# FMC_HPC2_RTM.net
KiCad netlist of a schematic drawn in Altium Designer
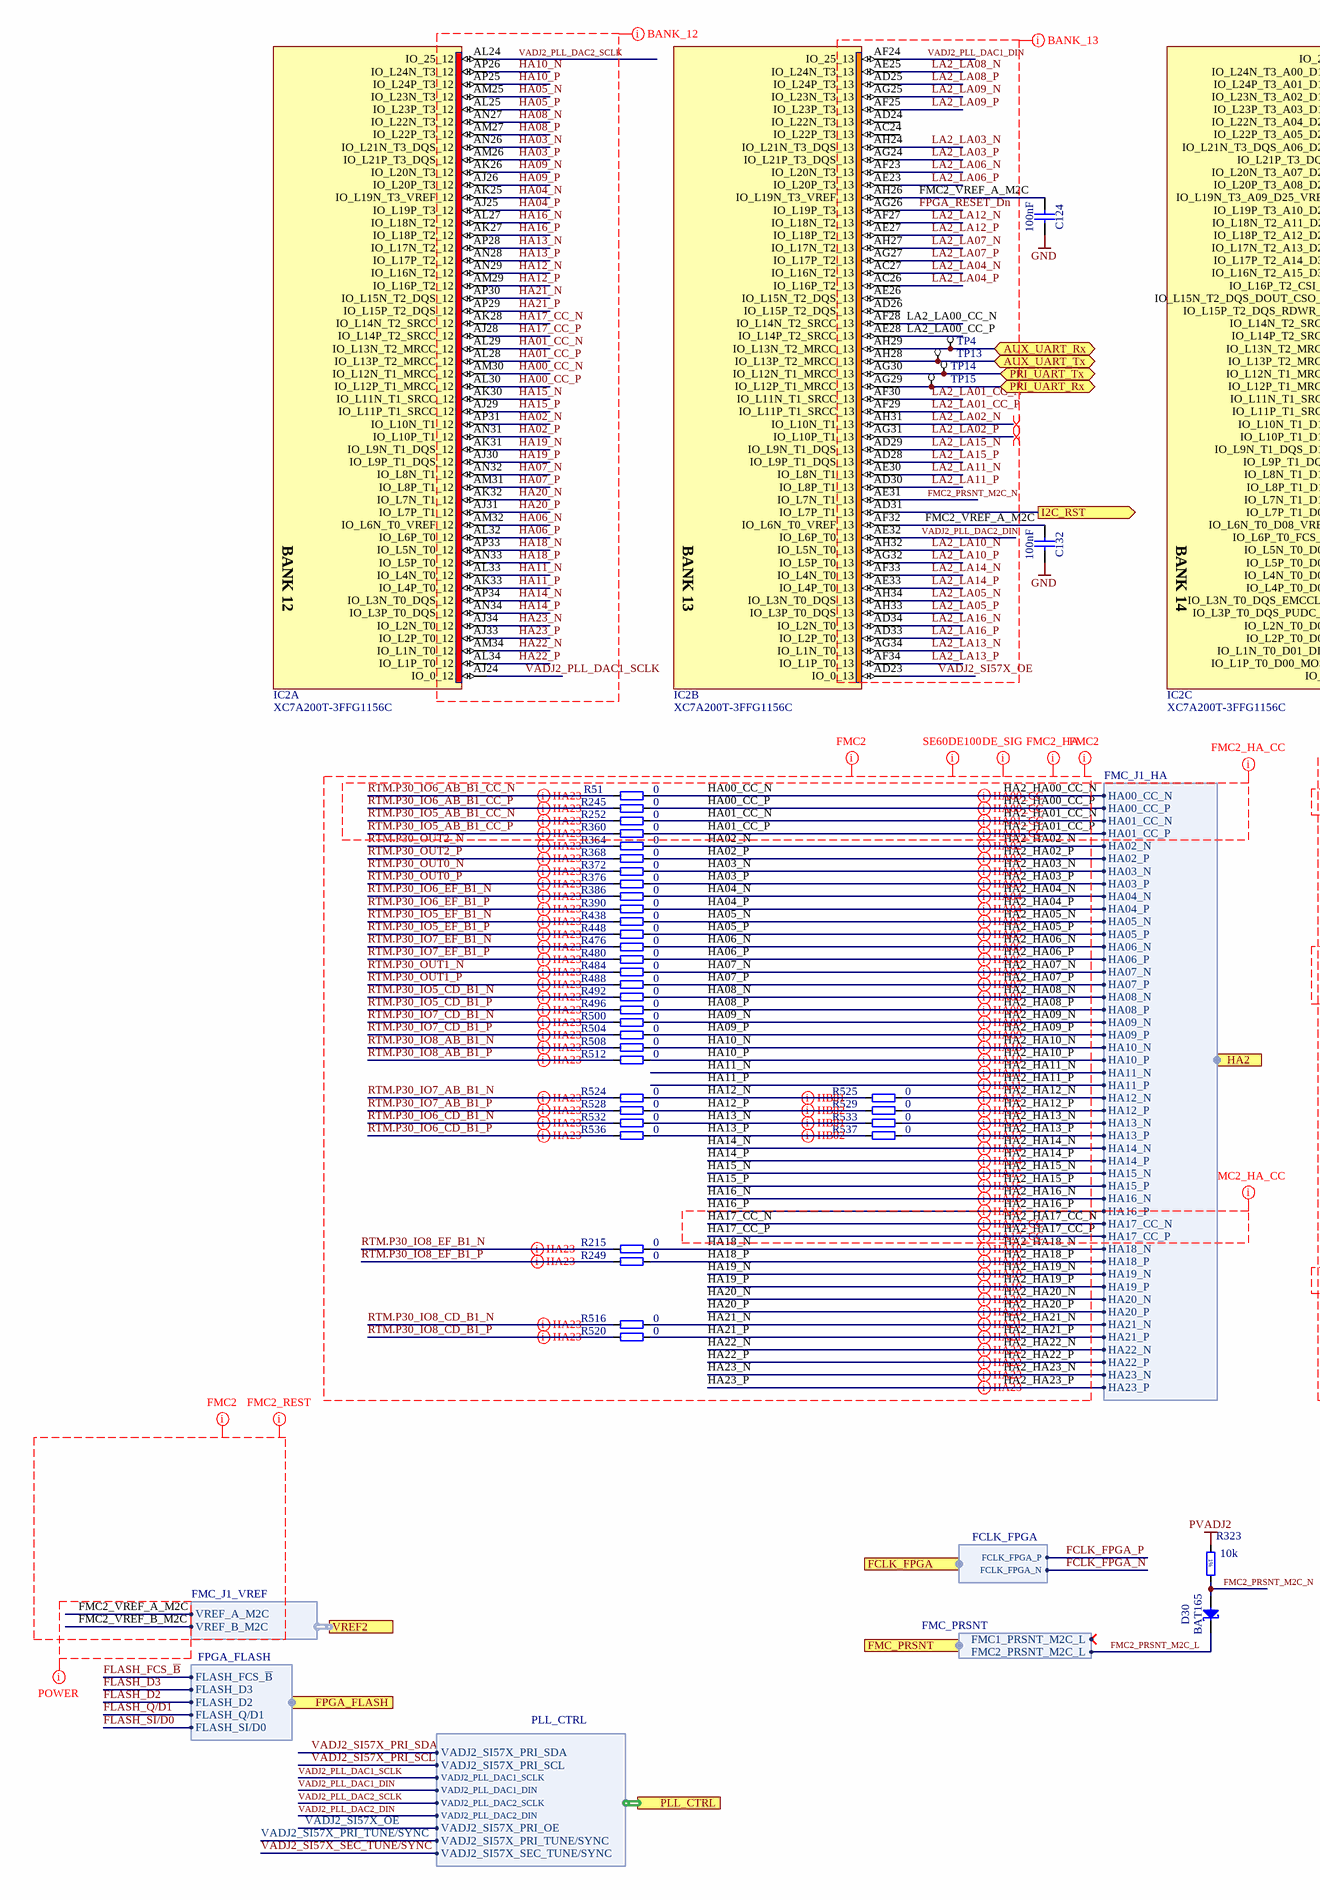
[diagram p0: FMC_HPC2_RTM.SchDoc, left]
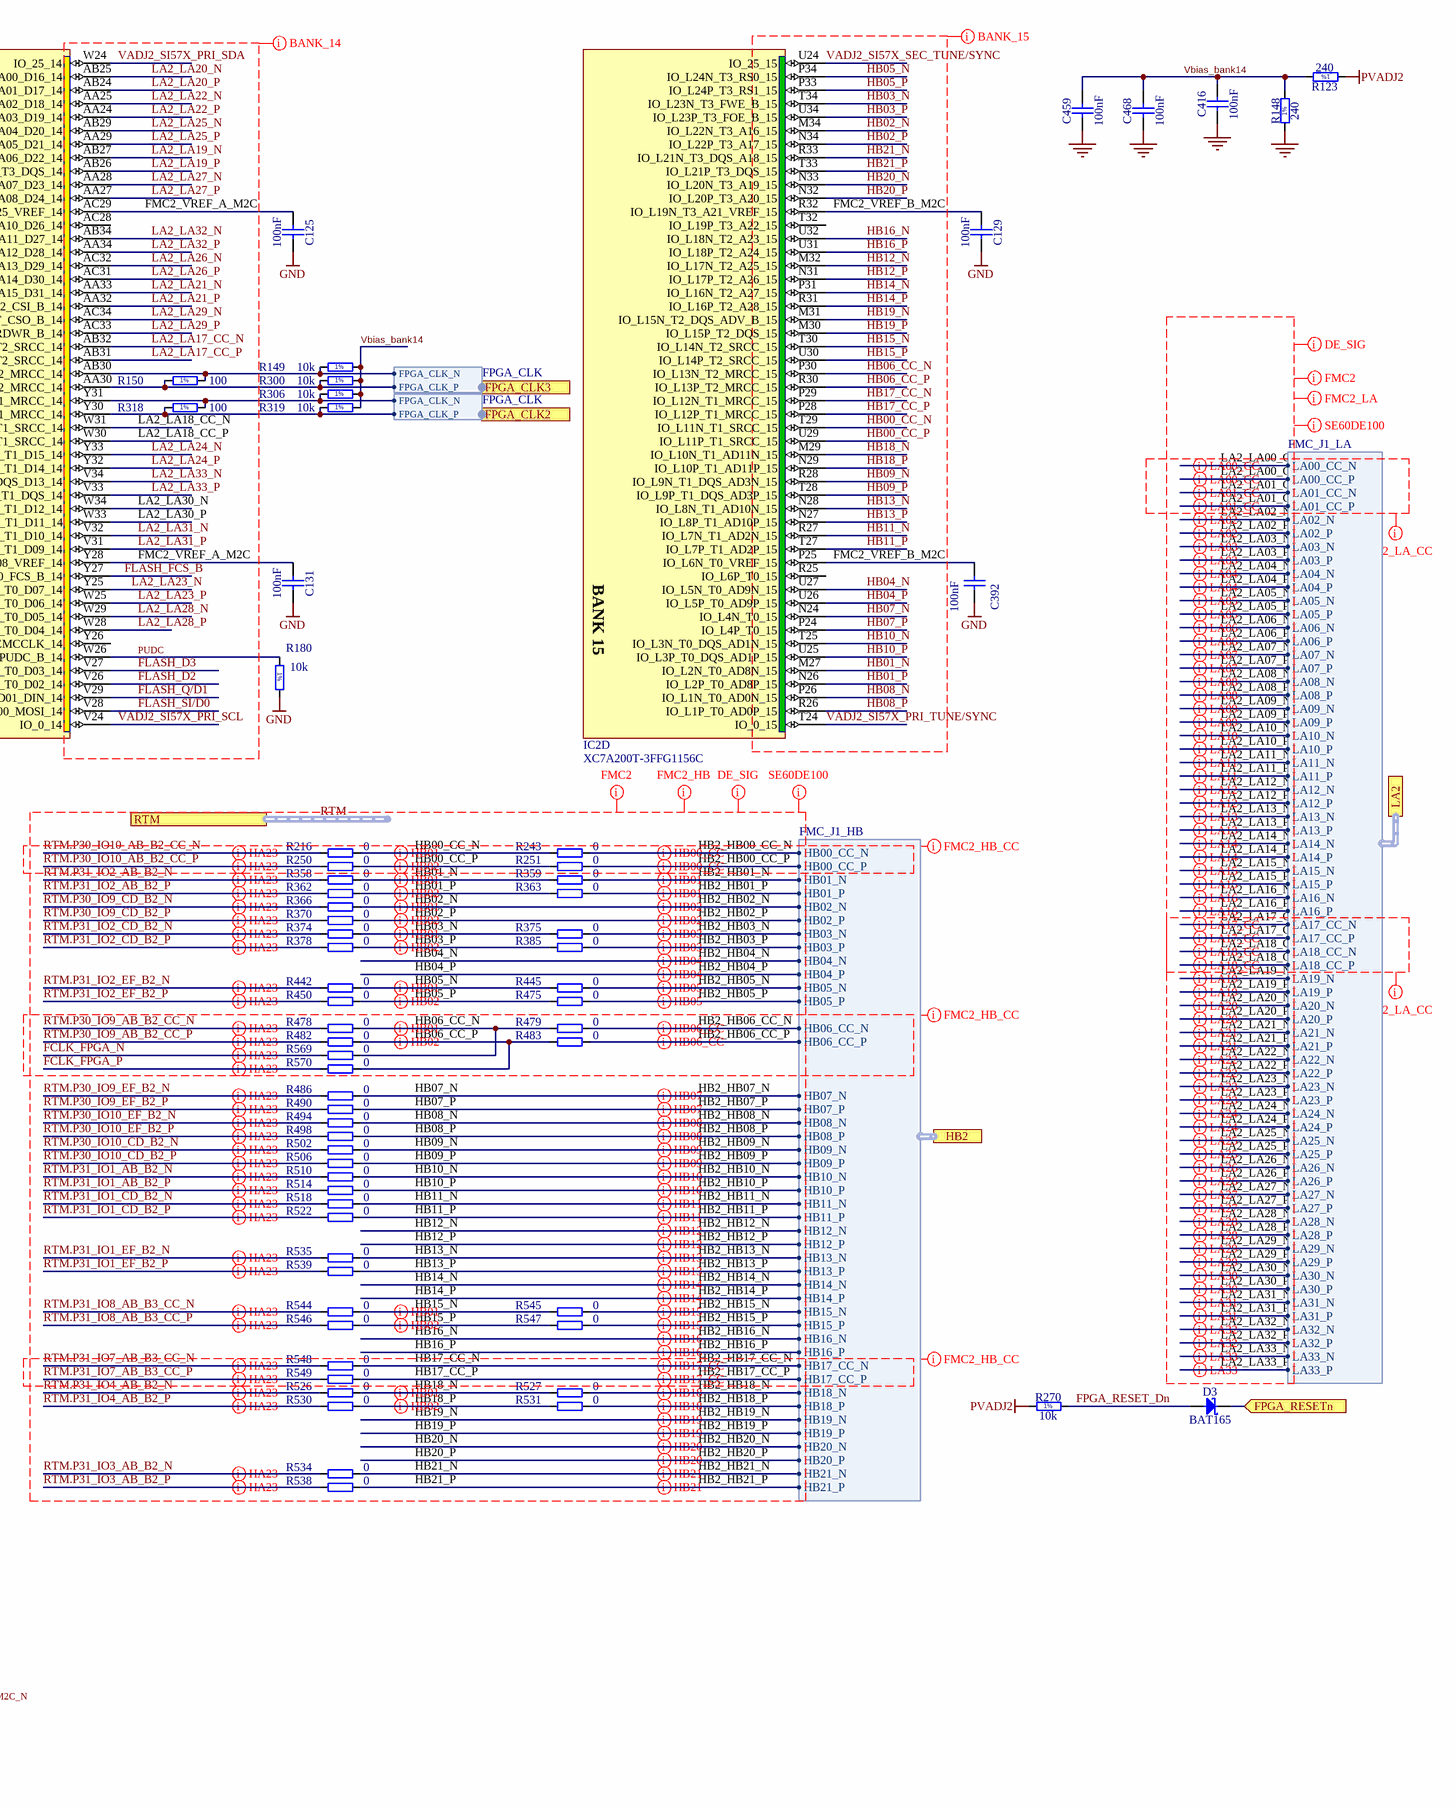
[diagram p1: FMC_HPC2_RTM.SchDoc, right]

(export (version "E")
  (design (tool "Eeschema 10.0.6"))
  (components
    (comp (ref "C124")
      (value "100nF")
      (footprint "CAPC0603X33N")
      (description "Non-polarised capacitor")
      (fields
        (field (name "PART NUMBER") "CC0201_100NF_6.3V_10%_X5R")
        (field (name "VOLTAGE") "6.3V")
        (field (name "AUTHOR") "CERN DEM JLC")
      )
      (libsource (lib "Capacitors") (part "Capacitor - non polarized"))
    )
    (comp (ref "C125")
      (value "100nF")
      (footprint "CAPC0603X33N")
      (description "Non-polarised capacitor")
      (fields
        (field (name "PART NUMBER") "CC0201_100NF_6.3V_10%_X5R")
        (field (name "VOLTAGE") "6.3V")
        (field (name "AUTHOR") "CERN DEM JLC")
      )
      (libsource (lib "Capacitors") (part "Capacitor - non polarized"))
    )
    (comp (ref "C129")
      (value "100nF")
      (footprint "CAPC0603X33N")
      (description "Non-polarised capacitor")
      (fields
        (field (name "PART NUMBER") "CC0201_100NF_6.3V_10%_X5R")
        (field (name "VOLTAGE") "6.3V")
        (field (name "AUTHOR") "CERN DEM JLC")
      )
      (libsource (lib "Capacitors") (part "Capacitor - non polarized"))
    )
    (comp (ref "C131")
      (value "100nF")
      (footprint "CAPC0603X33N")
      (description "Non-polarised capacitor")
      (fields
        (field (name "PART NUMBER") "CC0201_100NF_6.3V_10%_X5R")
        (field (name "VOLTAGE") "6.3V")
        (field (name "AUTHOR") "CERN DEM JLC")
      )
      (libsource (lib "Capacitors") (part "Capacitor - non polarized"))
    )
    (comp (ref "C132")
      (value "100nF")
      (footprint "CAPC0603X33N")
      (description "Non-polarised capacitor")
      (fields
        (field (name "PART NUMBER") "CC0201_100NF_6.3V_10%_X5R")
        (field (name "VOLTAGE") "6.3V")
        (field (name "AUTHOR") "CERN DEM JLC")
      )
      (libsource (lib "Capacitors") (part "Capacitor - non polarized"))
    )
    (comp (ref "C392")
      (value "100nF")
      (footprint "CAPC0603X33N")
      (description "Non-polarised capacitor")
      (fields
        (field (name "PART NUMBER") "CC0201_100NF_6.3V_10%_X5R")
        (field (name "VOLTAGE") "6.3V")
        (field (name "AUTHOR") "CERN DEM JLC")
      )
      (libsource (lib "Capacitors") (part "Capacitor - non polarized"))
    )
    (comp (ref "C416")
      (value "100nF")
      (footprint "CAPC0603X33N")
      (description "Non-polarised capacitor")
      (fields
        (field (name "MANUFACTURER PART NUMBER") "CC0201_100NF_6.3V_10%_X5R")
        (field (name "MANUFACTURER") "GENERIC")
        (field (name "AUTHOR") "CERN DEM JLC")
      )
      (libsource (lib "Capacitors") (part "Capacitor - non polarized"))
    )
    (comp (ref "C459")
      (value "100nF")
      (footprint "CAPC0603X33N")
      (description "Non-polarised capacitor")
      (fields
        (field (name "MANUFACTURER PART NUMBER") "CC0201_100NF_6.3V_10%_X5R")
        (field (name "MANUFACTURER") "GENERIC")
        (field (name "AUTHOR") "CERN DEM JLC")
      )
      (libsource (lib "Capacitors") (part "Capacitor - non polarized"))
    )
    (comp (ref "C468")
      (value "100nF")
      (footprint "CAPC0603X33N")
      (description "Non-polarised capacitor")
      (fields
        (field (name "MANUFACTURER PART NUMBER") "CC0201_100NF_6.3V_10%_X5R")
        (field (name "MANUFACTURER") "GENERIC")
        (field (name "AUTHOR") "CERN DEM JLC")
      )
      (libsource (lib "Capacitors") (part "Capacitor - non polarized"))
    )
    (comp (ref "D3")
      (value "BAT165")
      (footprint "SOD2512X110N")
      (description "Schottky Diode")
      (fields
        (field (name "VOLTAGE") "40V")
        (field (name "POWER") "750mA")
        (field (name "AUTHOR") "CERN DEM JLC")
      )
      (libsource (lib "ICs And Semiconductors") (part "Diode Schottky"))
    )
    (comp (ref "D30")
      (value "BAT165")
      (footprint "SOD2512X110N")
      (description "Schottky Diode")
      (fields
        (field (name "MANUFACTURER") "INFINEON")
        (field (name "VOLTAGE") "40V")
        (field (name "AUTHOR") "CERN DEM JLC")
      )
      (libsource (lib "ICs And Semiconductors") (part "Diode Schottky"))
    )
    (comp (ref "IC2")
      (value "XC7A200T-3FFG1156C")
      (footprint "BGA1156C100P34X34_3500X3500X335")
      (description "Artix-6 FPGA, 16 GTPs, 600 User I/Os, 1156-Pin BGA, Speed Grade 2, Commercial Grade, Pb-Free")
      (fields
        (field (name "MANUFACTURER") "XILINX")
        (field (name "MANUFACTURER PART NUMBER") "XC7A350T-2FFG1156C")
        (field (name "AUTHOR") "CERN DEM JLC")
      )
      (libsource (lib "AMC_FMC_Carrier") (part "XC7A200T-3FFG1156C"))
    )
    (comp (ref "R51")
      (value "0")
      (footprint "RESC0603X28N")
      (description "Resistor")
      (fields
        (field (name "PART NUMBER") "R0201_0R_JUMPER")
        (field (name "MANUFACTURER") "GENERIC")
        (field (name "AUTHOR") "CERN DEM JLC")
      )
      (libsource (lib "Resistors") (part "Resistor"))
    )
    (comp (ref "R123")
      (value "240")
      (footprint "RESC1005X40N")
      (description "Resistor - 1%")
      (fields
        (field (name "MANUFACTURER PART NUMBER") "R0402_240R_1%_0.0625W_100PPM")
        (field (name "MANUFACTURER") "GENERIC")
        (field (name "AUTHOR") "CERN DEM JLC")
      )
      (libsource (lib "Resistors") (part "Resistor - 1%"))
    )
    (comp (ref "R148")
      (value "240")
      (footprint "RESC1005X40N")
      (description "Resistor - 1%")
      (fields
        (field (name "MANUFACTURER PART NUMBER") "R0402_240R_1%_0.0625W_100PPM")
        (field (name "MANUFACTURER") "GENERIC")
        (field (name "AUTHOR") "CERN DEM JLC")
      )
      (libsource (lib "Resistors") (part "Resistor - 1%"))
    )
    (comp (ref "R149")
      (value "10k")
      (footprint "RESC1005X40N")
      (description "Resistor - 1%")
      (fields
        (field (name "MANUFACTURER PART NUMBER") "R0402_10K_1%_0.0625W_100PPM")
        (field (name "MANUFACTURER") "GENERIC")
        (field (name "AUTHOR") "CERN DEM JLC")
      )
      (libsource (lib "Resistors") (part "Resistor - 1%"))
    )
    (comp (ref "R150")
      (value "100")
      (footprint "RESC0603X28N")
      (description "Resistor - 1%")
      (fields
        (field (name "MANUFACTURER PART NUMBER") "R0201_100R_1%_0.05W_200PPM")
        (field (name "MANUFACTURER") "GENERIC")
        (field (name "AUTHOR") "CERN DEM JLC")
      )
      (libsource (lib "Resistors") (part "Resistor - 1%"))
    )
    (comp (ref "R180")
      (value "10k")
      (footprint "RESC1005X40N")
      (description "Resistor - 1%")
      (fields
        (field (name "PART NUMBER") "R0402_10K_1%_0.0625W_100PPM")
        (field (name "POWER") "0.0625W")
        (field (name "AUTHOR") "CERN DEM JLC")
      )
      (libsource (lib "Resistors") (part "Resistor - 1%"))
    )
    (comp (ref "R215")
      (value "0")
      (footprint "RESC0603X28N")
      (description "Resistor")
      (fields
        (field (name "PART NUMBER") "R0201_0R_JUMPER")
        (field (name "MANUFACTURER") "GENERIC")
        (field (name "AUTHOR") "CERN DEM JLC")
      )
      (libsource (lib "Resistors") (part "Resistor"))
    )
    (comp (ref "R216")
      (value "0")
      (footprint "RESC0603X28N")
      (description "Resistor")
      (fields
        (field (name "PART NUMBER") "R0201_0R_JUMPER")
        (field (name "MANUFACTURER") "GENERIC")
        (field (name "AUTHOR") "CERN DEM JLC")
      )
      (libsource (lib "Resistors") (part "Resistor"))
    )
    (comp (ref "R243")
      (value "0")
      (footprint "RESC0603X28N")
      (description "Resistor")
      (fields
        (field (name "PART NUMBER") "R0201_0R_JUMPER")
        (field (name "MANUFACTURER") "GENERIC")
        (field (name "AUTHOR") "CERN DEM JLC")
      )
      (libsource (lib "Resistors") (part "Resistor"))
    )
    (comp (ref "R245")
      (value "0")
      (footprint "RESC0603X28N")
      (description "Resistor")
      (fields
        (field (name "PART NUMBER") "R0201_0R_JUMPER")
        (field (name "MANUFACTURER") "GENERIC")
        (field (name "AUTHOR") "CERN DEM JLC")
      )
      (libsource (lib "Resistors") (part "Resistor"))
    )
    (comp (ref "R249")
      (value "0")
      (footprint "RESC0603X28N")
      (description "Resistor")
      (fields
        (field (name "PART NUMBER") "R0201_0R_JUMPER")
        (field (name "MANUFACTURER") "GENERIC")
        (field (name "AUTHOR") "CERN DEM JLC")
      )
      (libsource (lib "Resistors") (part "Resistor"))
    )
    (comp (ref "R250")
      (value "0")
      (footprint "RESC0603X28N")
      (description "Resistor")
      (fields
        (field (name "PART NUMBER") "R0201_0R_JUMPER")
        (field (name "MANUFACTURER") "GENERIC")
        (field (name "AUTHOR") "CERN DEM JLC")
      )
      (libsource (lib "Resistors") (part "Resistor"))
    )
    (comp (ref "R251")
      (value "0")
      (footprint "RESC0603X28N")
      (description "Resistor")
      (fields
        (field (name "PART NUMBER") "R0201_0R_JUMPER")
        (field (name "MANUFACTURER") "GENERIC")
        (field (name "AUTHOR") "CERN DEM JLC")
      )
      (libsource (lib "Resistors") (part "Resistor"))
    )
    (comp (ref "R252")
      (value "0")
      (footprint "RESC0603X28N")
      (description "Resistor")
      (fields
        (field (name "PART NUMBER") "R0201_0R_JUMPER")
        (field (name "MANUFACTURER") "GENERIC")
        (field (name "AUTHOR") "CERN DEM JLC")
      )
      (libsource (lib "Resistors") (part "Resistor"))
    )
    (comp (ref "R270")
      (value "10k")
      (footprint "RESC1005X40N")
      (description "Resistor - 1%")
      (fields
        (field (name "PART NUMBER") "R0402_10K_1%_0.0625W_100PPM")
        (field (name "POWER") "0.0625W")
        (field (name "AUTHOR") "CERN DEM JLC")
      )
      (libsource (lib "Resistors") (part "Resistor - 1%"))
    )
    (comp (ref "R300")
      (value "10k")
      (footprint "RESC1005X40N")
      (description "Resistor - 1%")
      (fields
        (field (name "MANUFACTURER PART NUMBER") "R0402_10K_1%_0.0625W_100PPM")
        (field (name "MANUFACTURER") "GENERIC")
        (field (name "AUTHOR") "CERN DEM JLC")
      )
      (libsource (lib "Resistors") (part "Resistor - 1%"))
    )
    (comp (ref "R306")
      (value "10k")
      (footprint "RESC1005X40N")
      (description "Resistor - 1%")
      (fields
        (field (name "MANUFACTURER PART NUMBER") "R0402_10K_1%_0.0625W_100PPM")
        (field (name "MANUFACTURER") "GENERIC")
        (field (name "AUTHOR") "CERN DEM JLC")
      )
      (libsource (lib "Resistors") (part "Resistor - 1%"))
    )
    (comp (ref "R318")
      (value "100")
      (footprint "RESC0603X28N")
      (description "Resistor - 1%")
      (fields
        (field (name "MANUFACTURER PART NUMBER") "R0201_100R_1%_0.05W_200PPM")
        (field (name "MANUFACTURER") "GENERIC")
        (field (name "AUTHOR") "CERN DEM JLC")
      )
      (libsource (lib "Resistors") (part "Resistor - 1%"))
    )
    (comp (ref "R319")
      (value "10k")
      (footprint "RESC1005X40N")
      (description "Resistor - 1%")
      (fields
        (field (name "MANUFACTURER PART NUMBER") "R0402_10K_1%_0.0625W_100PPM")
        (field (name "MANUFACTURER") "GENERIC")
        (field (name "AUTHOR") "CERN DEM JLC")
      )
      (libsource (lib "Resistors") (part "Resistor - 1%"))
    )
    (comp (ref "R323")
      (value "10k")
      (footprint "RESC1005X40N")
      (description "Resistor - 1%")
      (fields
        (field (name "PART NUMBER") "R0402_10K_1%_0.0625W_100PPM")
        (field (name "POWER") "0.0625W")
        (field (name "AUTHOR") "CERN DEM JLC")
      )
      (libsource (lib "Resistors") (part "Resistor - 1%"))
    )
    (comp (ref "R358")
      (value "0")
      (footprint "RESC0603X28N")
      (description "Resistor")
      (fields
        (field (name "PART NUMBER") "R0201_0R_JUMPER")
        (field (name "MANUFACTURER") "GENERIC")
        (field (name "AUTHOR") "CERN DEM JLC")
      )
      (libsource (lib "Resistors") (part "Resistor"))
    )
    (comp (ref "R359")
      (value "0")
      (footprint "RESC0603X28N")
      (description "Resistor")
      (fields
        (field (name "PART NUMBER") "R0201_0R_JUMPER")
        (field (name "MANUFACTURER") "GENERIC")
        (field (name "AUTHOR") "CERN DEM JLC")
      )
      (libsource (lib "Resistors") (part "Resistor"))
    )
    (comp (ref "R360")
      (value "0")
      (footprint "RESC0603X28N")
      (description "Resistor")
      (fields
        (field (name "PART NUMBER") "R0201_0R_JUMPER")
        (field (name "MANUFACTURER") "GENERIC")
        (field (name "AUTHOR") "CERN DEM JLC")
      )
      (libsource (lib "Resistors") (part "Resistor"))
    )
    (comp (ref "R362")
      (value "0")
      (footprint "RESC0603X28N")
      (description "Resistor")
      (fields
        (field (name "PART NUMBER") "R0201_0R_JUMPER")
        (field (name "MANUFACTURER") "GENERIC")
        (field (name "AUTHOR") "CERN DEM JLC")
      )
      (libsource (lib "Resistors") (part "Resistor"))
    )
    (comp (ref "R363")
      (value "0")
      (footprint "RESC0603X28N")
      (description "Resistor")
      (fields
        (field (name "PART NUMBER") "R0201_0R_JUMPER")
        (field (name "MANUFACTURER") "GENERIC")
        (field (name "AUTHOR") "CERN DEM JLC")
      )
      (libsource (lib "Resistors") (part "Resistor"))
    )
    (comp (ref "R364")
      (value "0")
      (footprint "RESC0603X28N")
      (description "Resistor")
      (fields
        (field (name "PART NUMBER") "R0201_0R_JUMPER")
        (field (name "MANUFACTURER") "GENERIC")
        (field (name "AUTHOR") "CERN DEM JLC")
      )
      (libsource (lib "Resistors") (part "Resistor"))
    )
    (comp (ref "R366")
      (value "0")
      (footprint "RESC0603X28N")
      (description "Resistor")
      (fields
        (field (name "PART NUMBER") "R0201_0R_JUMPER")
        (field (name "MANUFACTURER") "GENERIC")
        (field (name "AUTHOR") "CERN DEM JLC")
      )
      (libsource (lib "Resistors") (part "Resistor"))
    )
    (comp (ref "R368")
      (value "0")
      (footprint "RESC0603X28N")
      (description "Resistor")
      (fields
        (field (name "PART NUMBER") "R0201_0R_JUMPER")
        (field (name "MANUFACTURER") "GENERIC")
        (field (name "AUTHOR") "CERN DEM JLC")
      )
      (libsource (lib "Resistors") (part "Resistor"))
    )
    (comp (ref "R370")
      (value "0")
      (footprint "RESC0603X28N")
      (description "Resistor")
      (fields
        (field (name "PART NUMBER") "R0201_0R_JUMPER")
        (field (name "MANUFACTURER") "GENERIC")
        (field (name "AUTHOR") "CERN DEM JLC")
      )
      (libsource (lib "Resistors") (part "Resistor"))
    )
    (comp (ref "R372")
      (value "0")
      (footprint "RESC0603X28N")
      (description "Resistor")
      (fields
        (field (name "PART NUMBER") "R0201_0R_JUMPER")
        (field (name "MANUFACTURER") "GENERIC")
        (field (name "AUTHOR") "CERN DEM JLC")
      )
      (libsource (lib "Resistors") (part "Resistor"))
    )
    (comp (ref "R374")
      (value "0")
      (footprint "RESC0603X28N")
      (description "Resistor")
      (fields
        (field (name "PART NUMBER") "R0201_0R_JUMPER")
        (field (name "MANUFACTURER") "GENERIC")
        (field (name "AUTHOR") "CERN DEM JLC")
      )
      (libsource (lib "Resistors") (part "Resistor"))
    )
    (comp (ref "R375")
      (value "0")
      (footprint "RESC0603X28N")
      (description "Resistor")
      (fields
        (field (name "PART NUMBER") "R0201_0R_JUMPER")
        (field (name "MANUFACTURER") "GENERIC")
        (field (name "AUTHOR") "CERN DEM JLC")
      )
      (libsource (lib "Resistors") (part "Resistor"))
    )
    (comp (ref "R376")
      (value "0")
      (footprint "RESC0603X28N")
      (description "Resistor")
      (fields
        (field (name "PART NUMBER") "R0201_0R_JUMPER")
        (field (name "MANUFACTURER") "GENERIC")
        (field (name "AUTHOR") "CERN DEM JLC")
      )
      (libsource (lib "Resistors") (part "Resistor"))
    )
    (comp (ref "R378")
      (value "0")
      (footprint "RESC0603X28N")
      (description "Resistor")
      (fields
        (field (name "PART NUMBER") "R0201_0R_JUMPER")
        (field (name "MANUFACTURER") "GENERIC")
        (field (name "AUTHOR") "CERN DEM JLC")
      )
      (libsource (lib "Resistors") (part "Resistor"))
    )
    (comp (ref "R385")
      (value "0")
      (footprint "RESC0603X28N")
      (description "Resistor")
      (fields
        (field (name "PART NUMBER") "R0201_0R_JUMPER")
        (field (name "MANUFACTURER") "GENERIC")
        (field (name "AUTHOR") "CERN DEM JLC")
      )
      (libsource (lib "Resistors") (part "Resistor"))
    )
    (comp (ref "R386")
      (value "0")
      (footprint "RESC0603X28N")
      (description "Resistor")
      (fields
        (field (name "PART NUMBER") "R0201_0R_JUMPER")
        (field (name "MANUFACTURER") "GENERIC")
        (field (name "AUTHOR") "CERN DEM JLC")
      )
      (libsource (lib "Resistors") (part "Resistor"))
    )
    (comp (ref "R390")
      (value "0")
      (footprint "RESC0603X28N")
      (description "Resistor")
      (fields
        (field (name "PART NUMBER") "R0201_0R_JUMPER")
        (field (name "MANUFACTURER") "GENERIC")
        (field (name "AUTHOR") "CERN DEM JLC")
      )
      (libsource (lib "Resistors") (part "Resistor"))
    )
    (comp (ref "R438")
      (value "0")
      (footprint "RESC0603X28N")
      (description "Resistor")
      (fields
        (field (name "PART NUMBER") "R0201_0R_JUMPER")
        (field (name "MANUFACTURER") "GENERIC")
        (field (name "AUTHOR") "CERN DEM JLC")
      )
      (libsource (lib "Resistors") (part "Resistor"))
    )
    (comp (ref "R442")
      (value "0")
      (footprint "RESC0603X28N")
      (description "Resistor")
      (fields
        (field (name "PART NUMBER") "R0201_0R_JUMPER")
        (field (name "MANUFACTURER") "GENERIC")
        (field (name "AUTHOR") "CERN DEM JLC")
      )
      (libsource (lib "Resistors") (part "Resistor"))
    )
    (comp (ref "R445")
      (value "0")
      (footprint "RESC0603X28N")
      (description "Resistor")
      (fields
        (field (name "PART NUMBER") "R0201_0R_JUMPER")
        (field (name "MANUFACTURER") "GENERIC")
        (field (name "AUTHOR") "CERN DEM JLC")
      )
      (libsource (lib "Resistors") (part "Resistor"))
    )
    (comp (ref "R448")
      (value "0")
      (footprint "RESC0603X28N")
      (description "Resistor")
      (fields
        (field (name "PART NUMBER") "R0201_0R_JUMPER")
        (field (name "MANUFACTURER") "GENERIC")
        (field (name "AUTHOR") "CERN DEM JLC")
      )
      (libsource (lib "Resistors") (part "Resistor"))
    )
    (comp (ref "R450")
      (value "0")
      (footprint "RESC0603X28N")
      (description "Resistor")
      (fields
        (field (name "PART NUMBER") "R0201_0R_JUMPER")
        (field (name "MANUFACTURER") "GENERIC")
        (field (name "AUTHOR") "CERN DEM JLC")
      )
      (libsource (lib "Resistors") (part "Resistor"))
    )
    (comp (ref "R475")
      (value "0")
      (footprint "RESC0603X28N")
      (description "Resistor")
      (fields
        (field (name "PART NUMBER") "R0201_0R_JUMPER")
        (field (name "MANUFACTURER") "GENERIC")
        (field (name "AUTHOR") "CERN DEM JLC")
      )
      (libsource (lib "Resistors") (part "Resistor"))
    )
    (comp (ref "R476")
      (value "0")
      (footprint "RESC0603X28N")
      (description "Resistor")
      (fields
        (field (name "PART NUMBER") "R0201_0R_JUMPER")
        (field (name "MANUFACTURER") "GENERIC")
        (field (name "AUTHOR") "CERN DEM JLC")
      )
      (libsource (lib "Resistors") (part "Resistor"))
    )
    (comp (ref "R478")
      (value "0")
      (footprint "RESC0603X28N")
      (description "Resistor")
      (fields
        (field (name "PART NUMBER") "R0201_0R_JUMPER")
        (field (name "MANUFACTURER") "GENERIC")
        (field (name "AUTHOR") "CERN DEM JLC")
      )
      (libsource (lib "Resistors") (part "Resistor"))
    )
    (comp (ref "R479")
      (value "0")
      (footprint "RESC0603X28N")
      (description "Resistor")
      (fields
        (field (name "PART NUMBER") "R0201_0R_JUMPER")
        (field (name "MANUFACTURER") "GENERIC")
        (field (name "AUTHOR") "CERN DEM JLC")
      )
      (libsource (lib "Resistors") (part "Resistor"))
    )
    (comp (ref "R480")
      (value "0")
      (footprint "RESC0603X28N")
      (description "Resistor")
      (fields
        (field (name "PART NUMBER") "R0201_0R_JUMPER")
        (field (name "MANUFACTURER") "GENERIC")
        (field (name "AUTHOR") "CERN DEM JLC")
      )
      (libsource (lib "Resistors") (part "Resistor"))
    )
    (comp (ref "R482")
      (value "0")
      (footprint "RESC0603X28N")
      (description "Resistor")
      (fields
        (field (name "PART NUMBER") "R0201_0R_JUMPER")
        (field (name "MANUFACTURER") "GENERIC")
        (field (name "AUTHOR") "CERN DEM JLC")
      )
      (libsource (lib "Resistors") (part "Resistor"))
    )
    (comp (ref "R483")
      (value "0")
      (footprint "RESC0603X28N")
      (description "Resistor")
      (fields
        (field (name "PART NUMBER") "R0201_0R_JUMPER")
        (field (name "MANUFACTURER") "GENERIC")
        (field (name "AUTHOR") "CERN DEM JLC")
      )
      (libsource (lib "Resistors") (part "Resistor"))
    )
    (comp (ref "R484")
      (value "0")
      (footprint "RESC0603X28N")
      (description "Resistor")
      (fields
        (field (name "PART NUMBER") "R0201_0R_JUMPER")
        (field (name "MANUFACTURER") "GENERIC")
        (field (name "AUTHOR") "CERN DEM JLC")
      )
      (libsource (lib "Resistors") (part "Resistor"))
    )
    (comp (ref "R486")
      (value "0")
      (footprint "RESC0603X28N")
      (description "Resistor")
      (fields
        (field (name "PART NUMBER") "R0201_0R_JUMPER")
        (field (name "MANUFACTURER") "GENERIC")
        (field (name "AUTHOR") "CERN DEM JLC")
      )
      (libsource (lib "Resistors") (part "Resistor"))
    )
    (comp (ref "R488")
      (value "0")
      (footprint "RESC0603X28N")
      (description "Resistor")
      (fields
        (field (name "PART NUMBER") "R0201_0R_JUMPER")
        (field (name "MANUFACTURER") "GENERIC")
        (field (name "AUTHOR") "CERN DEM JLC")
      )
      (libsource (lib "Resistors") (part "Resistor"))
    )
    (comp (ref "R490")
      (value "0")
      (footprint "RESC0603X28N")
      (description "Resistor")
      (fields
        (field (name "PART NUMBER") "R0201_0R_JUMPER")
        (field (name "MANUFACTURER") "GENERIC")
        (field (name "AUTHOR") "CERN DEM JLC")
      )
      (libsource (lib "Resistors") (part "Resistor"))
    )
    (comp (ref "R492")
      (value "0")
      (footprint "RESC0603X28N")
      (description "Resistor")
      (fields
        (field (name "PART NUMBER") "R0201_0R_JUMPER")
        (field (name "MANUFACTURER") "GENERIC")
        (field (name "AUTHOR") "CERN DEM JLC")
      )
      (libsource (lib "Resistors") (part "Resistor"))
    )
    (comp (ref "R494")
      (value "0")
      (footprint "RESC0603X28N")
      (description "Resistor")
      (fields
        (field (name "PART NUMBER") "R0201_0R_JUMPER")
        (field (name "MANUFACTURER") "GENERIC")
        (field (name "AUTHOR") "CERN DEM JLC")
      )
      (libsource (lib "Resistors") (part "Resistor"))
    )
    (comp (ref "R496")
      (value "0")
      (footprint "RESC0603X28N")
      (description "Resistor")
      (fields
        (field (name "PART NUMBER") "R0201_0R_JUMPER")
        (field (name "MANUFACTURER") "GENERIC")
        (field (name "AUTHOR") "CERN DEM JLC")
      )
      (libsource (lib "Resistors") (part "Resistor"))
    )
    (comp (ref "R498")
      (value "0")
      (footprint "RESC0603X28N")
      (description "Resistor")
      (fields
        (field (name "PART NUMBER") "R0201_0R_JUMPER")
        (field (name "MANUFACTURER") "GENERIC")
        (field (name "AUTHOR") "CERN DEM JLC")
      )
      (libsource (lib "Resistors") (part "Resistor"))
    )
    (comp (ref "R500")
      (value "0")
      (footprint "RESC0603X28N")
      (description "Resistor")
      (fields
        (field (name "PART NUMBER") "R0201_0R_JUMPER")
        (field (name "MANUFACTURER") "GENERIC")
        (field (name "AUTHOR") "CERN DEM JLC")
      )
      (libsource (lib "Resistors") (part "Resistor"))
    )
    (comp (ref "R502")
      (value "0")
      (footprint "RESC0603X28N")
      (description "Resistor")
      (fields
        (field (name "PART NUMBER") "R0201_0R_JUMPER")
        (field (name "MANUFACTURER") "GENERIC")
        (field (name "AUTHOR") "CERN DEM JLC")
      )
      (libsource (lib "Resistors") (part "Resistor"))
    )
    (comp (ref "R504")
      (value "0")
      (footprint "RESC0603X28N")
      (description "Resistor")
      (fields
        (field (name "PART NUMBER") "R0201_0R_JUMPER")
        (field (name "MANUFACTURER") "GENERIC")
        (field (name "AUTHOR") "CERN DEM JLC")
      )
      (libsource (lib "Resistors") (part "Resistor"))
    )
    (comp (ref "R506")
      (value "0")
      (footprint "RESC0603X28N")
      (description "Resistor")
      (fields
        (field (name "PART NUMBER") "R0201_0R_JUMPER")
        (field (name "MANUFACTURER") "GENERIC")
        (field (name "AUTHOR") "CERN DEM JLC")
      )
      (libsource (lib "Resistors") (part "Resistor"))
    )
    (comp (ref "R508")
      (value "0")
      (footprint "RESC0603X28N")
      (description "Resistor")
      (fields
        (field (name "PART NUMBER") "R0201_0R_JUMPER")
        (field (name "MANUFACTURER") "GENERIC")
        (field (name "AUTHOR") "CERN DEM JLC")
      )
      (libsource (lib "Resistors") (part "Resistor"))
    )
    (comp (ref "R510")
      (value "0")
      (footprint "RESC0603X28N")
      (description "Resistor")
      (fields
        (field (name "PART NUMBER") "R0201_0R_JUMPER")
        (field (name "MANUFACTURER") "GENERIC")
        (field (name "AUTHOR") "CERN DEM JLC")
      )
      (libsource (lib "Resistors") (part "Resistor"))
    )
    (comp (ref "R512")
      (value "0")
      (footprint "RESC0603X28N")
      (description "Resistor")
      (fields
        (field (name "PART NUMBER") "R0201_0R_JUMPER")
        (field (name "MANUFACTURER") "GENERIC")
        (field (name "AUTHOR") "CERN DEM JLC")
      )
      (libsource (lib "Resistors") (part "Resistor"))
    )
    (comp (ref "R514")
      (value "0")
      (footprint "RESC0603X28N")
      (description "Resistor")
      (fields
        (field (name "PART NUMBER") "R0201_0R_JUMPER")
        (field (name "MANUFACTURER") "GENERIC")
        (field (name "AUTHOR") "CERN DEM JLC")
      )
      (libsource (lib "Resistors") (part "Resistor"))
    )
    (comp (ref "R516")
      (value "0")
      (footprint "RESC0603X28N")
      (description "Resistor")
      (fields
        (field (name "PART NUMBER") "R0201_0R_JUMPER")
        (field (name "MANUFACTURER") "GENERIC")
        (field (name "AUTHOR") "CERN DEM JLC")
      )
      (libsource (lib "Resistors") (part "Resistor"))
    )
    (comp (ref "R518")
      (value "0")
      (footprint "RESC0603X28N")
      (description "Resistor")
      (fields
        (field (name "PART NUMBER") "R0201_0R_JUMPER")
        (field (name "MANUFACTURER") "GENERIC")
        (field (name "AUTHOR") "CERN DEM JLC")
      )
      (libsource (lib "Resistors") (part "Resistor"))
    )
    (comp (ref "R520")
      (value "0")
      (footprint "RESC0603X28N")
      (description "Resistor")
      (fields
        (field (name "PART NUMBER") "R0201_0R_JUMPER")
        (field (name "MANUFACTURER") "GENERIC")
        (field (name "AUTHOR") "CERN DEM JLC")
      )
      (libsource (lib "Resistors") (part "Resistor"))
    )
    (comp (ref "R522")
      (value "0")
      (footprint "RESC0603X28N")
      (description "Resistor")
      (fields
        (field (name "PART NUMBER") "R0201_0R_JUMPER")
        (field (name "MANUFACTURER") "GENERIC")
        (field (name "AUTHOR") "CERN DEM JLC")
      )
      (libsource (lib "Resistors") (part "Resistor"))
    )
    (comp (ref "R524")
      (value "0")
      (footprint "RESC0603X28N")
      (description "Resistor")
      (fields
        (field (name "PART NUMBER") "R0201_0R_JUMPER")
        (field (name "MANUFACTURER") "GENERIC")
        (field (name "AUTHOR") "CERN DEM JLC")
      )
      (libsource (lib "Resistors") (part "Resistor"))
    )
    (comp (ref "R525")
      (value "0")
      (footprint "RESC0603X28N")
      (description "Resistor")
      (fields
        (field (name "PART NUMBER") "R0201_0R_JUMPER")
        (field (name "MANUFACTURER") "GENERIC")
        (field (name "AUTHOR") "CERN DEM JLC")
      )
      (libsource (lib "Resistors") (part "Resistor"))
    )
    (comp (ref "R526")
      (value "0")
      (footprint "RESC0603X28N")
      (description "Resistor")
      (fields
        (field (name "PART NUMBER") "R0201_0R_JUMPER")
        (field (name "MANUFACTURER") "GENERIC")
        (field (name "AUTHOR") "CERN DEM JLC")
      )
      (libsource (lib "Resistors") (part "Resistor"))
    )
    (comp (ref "R527")
      (value "0")
      (footprint "RESC0603X28N")
      (description "Resistor")
      (fields
        (field (name "PART NUMBER") "R0201_0R_JUMPER")
        (field (name "MANUFACTURER") "GENERIC")
        (field (name "AUTHOR") "CERN DEM JLC")
      )
      (libsource (lib "Resistors") (part "Resistor"))
    )
    (comp (ref "R528")
      (value "0")
      (footprint "RESC0603X28N")
      (description "Resistor")
      (fields
        (field (name "PART NUMBER") "R0201_0R_JUMPER")
        (field (name "MANUFACTURER") "GENERIC")
        (field (name "AUTHOR") "CERN DEM JLC")
      )
      (libsource (lib "Resistors") (part "Resistor"))
    )
    (comp (ref "R529")
      (value "0")
      (footprint "RESC0603X28N")
      (description "Resistor")
      (fields
        (field (name "PART NUMBER") "R0201_0R_JUMPER")
        (field (name "MANUFACTURER") "GENERIC")
        (field (name "AUTHOR") "CERN DEM JLC")
      )
      (libsource (lib "Resistors") (part "Resistor"))
    )
    (comp (ref "R530")
      (value "0")
      (footprint "RESC0603X28N")
      (description "Resistor")
      (fields
        (field (name "PART NUMBER") "R0201_0R_JUMPER")
        (field (name "MANUFACTURER") "GENERIC")
        (field (name "AUTHOR") "CERN DEM JLC")
      )
      (libsource (lib "Resistors") (part "Resistor"))
    )
    (comp (ref "R531")
      (value "0")
      (footprint "RESC0603X28N")
      (description "Resistor")
      (fields
        (field (name "PART NUMBER") "R0201_0R_JUMPER")
        (field (name "MANUFACTURER") "GENERIC")
        (field (name "AUTHOR") "CERN DEM JLC")
      )
      (libsource (lib "Resistors") (part "Resistor"))
    )
    (comp (ref "R532")
      (value "0")
      (footprint "RESC0603X28N")
      (description "Resistor")
      (fields
        (field (name "PART NUMBER") "R0201_0R_JUMPER")
        (field (name "MANUFACTURER") "GENERIC")
        (field (name "AUTHOR") "CERN DEM JLC")
      )
      (libsource (lib "Resistors") (part "Resistor"))
    )
    (comp (ref "R533")
      (value "0")
      (footprint "RESC0603X28N")
      (description "Resistor")
      (fields
        (field (name "PART NUMBER") "R0201_0R_JUMPER")
        (field (name "MANUFACTURER") "GENERIC")
        (field (name "AUTHOR") "CERN DEM JLC")
      )
      (libsource (lib "Resistors") (part "Resistor"))
    )
    (comp (ref "R534")
      (value "0")
      (footprint "RESC0603X28N")
      (description "Resistor")
      (fields
        (field (name "PART NUMBER") "R0201_0R_JUMPER")
        (field (name "MANUFACTURER") "GENERIC")
        (field (name "AUTHOR") "CERN DEM JLC")
      )
      (libsource (lib "Resistors") (part "Resistor"))
    )
    (comp (ref "R535")
      (value "0")
      (footprint "RESC0603X28N")
      (description "Resistor")
      (fields
        (field (name "PART NUMBER") "R0201_0R_JUMPER")
        (field (name "MANUFACTURER") "GENERIC")
        (field (name "AUTHOR") "CERN DEM JLC")
      )
      (libsource (lib "Resistors") (part "Resistor"))
    )
    (comp (ref "R536")
      (value "0")
      (footprint "RESC0603X28N")
      (description "Resistor")
      (fields
        (field (name "PART NUMBER") "R0201_0R_JUMPER")
        (field (name "MANUFACTURER") "GENERIC")
        (field (name "AUTHOR") "CERN DEM JLC")
      )
      (libsource (lib "Resistors") (part "Resistor"))
    )
    (comp (ref "R537")
      (value "0")
      (footprint "RESC0603X28N")
      (description "Resistor")
      (fields
        (field (name "PART NUMBER") "R0201_0R_JUMPER")
        (field (name "MANUFACTURER") "GENERIC")
        (field (name "AUTHOR") "CERN DEM JLC")
      )
      (libsource (lib "Resistors") (part "Resistor"))
    )
    (comp (ref "R538")
      (value "0")
      (footprint "RESC0603X28N")
      (description "Resistor")
      (fields
        (field (name "PART NUMBER") "R0201_0R_JUMPER")
        (field (name "MANUFACTURER") "GENERIC")
        (field (name "AUTHOR") "CERN DEM JLC")
      )
      (libsource (lib "Resistors") (part "Resistor"))
    )
    (comp (ref "R539")
      (value "0")
      (footprint "RESC0603X28N")
      (description "Resistor")
      (fields
        (field (name "PART NUMBER") "R0201_0R_JUMPER")
        (field (name "MANUFACTURER") "GENERIC")
        (field (name "AUTHOR") "CERN DEM JLC")
      )
      (libsource (lib "Resistors") (part "Resistor"))
    )
    (comp (ref "R544")
      (value "0")
      (footprint "RESC0603X28N")
      (description "Resistor")
      (fields
        (field (name "PART NUMBER") "R0201_0R_JUMPER")
        (field (name "MANUFACTURER") "GENERIC")
        (field (name "AUTHOR") "CERN DEM JLC")
      )
      (libsource (lib "Resistors") (part "Resistor"))
    )
    (comp (ref "R545")
      (value "0")
      (footprint "RESC0603X28N")
      (description "Resistor")
      (fields
        (field (name "PART NUMBER") "R0201_0R_JUMPER")
        (field (name "MANUFACTURER") "GENERIC")
        (field (name "AUTHOR") "CERN DEM JLC")
      )
      (libsource (lib "Resistors") (part "Resistor"))
    )
    (comp (ref "R546")
      (value "0")
      (footprint "RESC0603X28N")
      (description "Resistor")
      (fields
        (field (name "PART NUMBER") "R0201_0R_JUMPER")
        (field (name "MANUFACTURER") "GENERIC")
        (field (name "AUTHOR") "CERN DEM JLC")
      )
      (libsource (lib "Resistors") (part "Resistor"))
    )
    (comp (ref "R547")
      (value "0")
      (footprint "RESC0603X28N")
      (description "Resistor")
      (fields
        (field (name "PART NUMBER") "R0201_0R_JUMPER")
        (field (name "MANUFACTURER") "GENERIC")
        (field (name "AUTHOR") "CERN DEM JLC")
      )
      (libsource (lib "Resistors") (part "Resistor"))
    )
    (comp (ref "R548")
      (value "0")
      (footprint "RESC0603X28N")
      (description "Resistor")
      (fields
        (field (name "PART NUMBER") "R0201_0R_JUMPER")
        (field (name "MANUFACTURER") "GENERIC")
        (field (name "AUTHOR") "CERN DEM JLC")
      )
      (libsource (lib "Resistors") (part "Resistor"))
    )
    (comp (ref "R549")
      (value "0")
      (footprint "RESC0603X28N")
      (description "Resistor")
      (fields
        (field (name "PART NUMBER") "R0201_0R_JUMPER")
        (field (name "MANUFACTURER") "GENERIC")
        (field (name "AUTHOR") "CERN DEM JLC")
      )
      (libsource (lib "Resistors") (part "Resistor"))
    )
    (comp (ref "R569")
      (value "0")
      (footprint "RESC0603X28N")
      (description "Resistor")
      (fields
        (field (name "PART NUMBER") "R0201_0R_JUMPER")
        (field (name "MANUFACTURER") "GENERIC")
        (field (name "AUTHOR") "CERN DEM JLC")
      )
      (libsource (lib "Resistors") (part "Resistor"))
    )
    (comp (ref "R570")
      (value "0")
      (footprint "RESC0603X28N")
      (description "Resistor")
      (fields
        (field (name "PART NUMBER") "R0201_0R_JUMPER")
        (field (name "MANUFACTURER") "GENERIC")
        (field (name "AUTHOR") "CERN DEM JLC")
      )
      (libsource (lib "Resistors") (part "Resistor"))
    )
    (comp (ref "TP4")
      (value "TP")
      (footprint "TP_large")
      (description "Testpoint")
      (libsource (lib "LIBRARY_SCH") (part "TP"))
    )
    (comp (ref "TP13")
      (value "TP")
      (footprint "TP_large")
      (description "Testpoint")
      (libsource (lib "LIBRARY_SCH") (part "TP"))
    )
    (comp (ref "TP14")
      (value "TP")
      (footprint "TP_large")
      (description "Testpoint")
      (libsource (lib "LIBRARY_SCH") (part "TP"))
    )
    (comp (ref "TP15")
      (value "TP")
      (footprint "TP_large")
      (description "Testpoint")
      (libsource (lib "LIBRARY_SCH") (part "TP"))
    )
  )
  (nets
    (net (code "12") (name "/AUX_UART_Rx") (class "Default")
      (node (ref "IC2") (pin "AH29") (pinfunction "IO_L13N_T2_MRCC_13_AH29") (pintype "bidirectional"))
      (node (ref "TP4") (pin "1") (pintype "passive"))
    )
    (net (code "13") (name "/AUX_UART_Tx") (class "Default")
      (node (ref "IC2") (pin "AH28") (pinfunction "IO_L13P_T2_MRCC_13_AH28") (pintype "bidirectional"))
      (node (ref "TP13") (pin "1") (pintype "passive"))
    )
    (net (code "14") (name "/FCLK_FPGA_N") (class "Default")
      (node (ref "R569") (pin "1") (pinfunction "1_1") (pintype "passive"))
    )
    (net (code "15") (name "/FCLK_FPGA_P") (class "Default")
      (node (ref "R570") (pin "1") (pinfunction "1_1") (pintype "passive"))
    )
    (net (code "16") (name "/FLASH_D2") (class "Default")
      (node (ref "IC2") (pin "V26") (pinfunction "IO_L2P_T0_D02_14_V26") (pintype "bidirectional"))
    )
    (net (code "17") (name "/FLASH_D3") (class "Default")
      (node (ref "IC2") (pin "V27") (pinfunction "IO_L2N_T0_D03_14_V27") (pintype "bidirectional"))
    )
    (net (code "18") (name "/FLASH_FCS_~{B}") (class "Default")
      (node (ref "IC2") (pin "Y27") (pinfunction "IO_L6P_T0_FCS_B_14_Y27") (pintype "bidirectional"))
    )
    (net (code "19") (name "/FLASH_Q{slash}D1") (class "Default")
      (node (ref "IC2") (pin "V29") (pinfunction "IO_L1N_T0_D01_DIN_14_V29") (pintype "bidirectional"))
    )
    (net (code "20") (name "/FLASH_SI{slash}D0") (class "Default")
      (node (ref "IC2") (pin "V28") (pinfunction "IO_L1P_T0_D00_MOSI_14_V28") (pintype "bidirectional"))
    )
    (net (code "21") (name "/FMC2_PRSNT_M2C_L") (class "Default")
      (node (ref "D30") (pin "1") (pinfunction "C_1") (pintype "passive"))
    )
    (net (code "22") (name "/FMC2_PRSNT_M2C_N") (class "Default")
      (node (ref "D30") (pin "2") (pinfunction "A_2") (pintype "passive"))
      (node (ref "IC2") (pin "AE31") (pinfunction "IO_L7N_T1_13_AE31") (pintype "bidirectional"))
      (node (ref "R323") (pin "2") (pinfunction "2_2") (pintype "passive"))
    )
    (net (code "23") (name "/FMC2_VREF_A_M2C") (class "Default")
      (node (ref "C124") (pin "1") (pinfunction "1_1") (pintype "passive"))
      (node (ref "C125") (pin "1") (pinfunction "1_1") (pintype "passive"))
      (node (ref "C131") (pin "1") (pinfunction "1_1") (pintype "passive"))
      (node (ref "C132") (pin "1") (pinfunction "1_1") (pintype "passive"))
      (node (ref "IC2") (pin "AC29") (pinfunction "IO_L19N_T3_A09_D25_VREF_14_AC29") (pintype "bidirectional"))
      (node (ref "IC2") (pin "AF32") (pinfunction "IO_L6N_T0_VREF_13_AF32") (pintype "bidirectional"))
      (node (ref "IC2") (pin "AH26") (pinfunction "IO_L19N_T3_VREF_13_AH26") (pintype "bidirectional"))
      (node (ref "IC2") (pin "Y28") (pinfunction "IO_L6N_T0_D08_VREF_14_Y28") (pintype "bidirectional"))
    )
    (net (code "24") (name "/FMC2_VREF_B_M2C") (class "Default")
      (node (ref "C129") (pin "1") (pinfunction "1_1") (pintype "passive"))
      (node (ref "C392") (pin "1") (pinfunction "1_1") (pintype "passive"))
      (node (ref "IC2") (pin "P25") (pinfunction "IO_L6N_T0_VREF_15_P25") (pintype "bidirectional"))
      (node (ref "IC2") (pin "R32") (pinfunction "IO_L19N_T3_A21_VREF_15_R32") (pintype "bidirectional"))
    )
    (net (code "26") (name "/FPGA_RESET_Dn") (class "Default")
      (node (ref "D3") (pin "2") (pinfunction "A_2") (pintype "passive"))
      (node (ref "IC2") (pin "AG26") (pinfunction "IO_L19P_T3_13_AG26") (pintype "bidirectional"))
      (node (ref "R270") (pin "2") (pinfunction "2_2") (pintype "passive"))
    )
    (net (code "27") (name "/FPGA_RESETn") (class "Default")
      (node (ref "D3") (pin "1") (pinfunction "C_1") (pintype "passive"))
    )
    (net (code "28") (name "/HA00_CC_N") (class "Default")
      (node (ref "IC2") (pin "AM30") (pinfunction "IO_L12N_T1_MRCC_12_AM30") (pintype "bidirectional"))
      (node (ref "R51") (pin "2") (pinfunction "2_2") (pintype "passive"))
    )
    (net (code "29") (name "/HA00_CC_P") (class "Default")
      (node (ref "IC2") (pin "AL30") (pinfunction "IO_L12P_T1_MRCC_12_AL30") (pintype "bidirectional"))
      (node (ref "R245") (pin "2") (pinfunction "2_2") (pintype "passive"))
    )
    (net (code "30") (name "/HA01_CC_N") (class "Default")
      (node (ref "IC2") (pin "AL29") (pinfunction "IO_L13N_T2_MRCC_12_AL29") (pintype "bidirectional"))
      (node (ref "R252") (pin "2") (pinfunction "2_2") (pintype "passive"))
    )
    (net (code "31") (name "/HA01_CC_P") (class "Default")
      (node (ref "IC2") (pin "AL28") (pinfunction "IO_L13P_T2_MRCC_12_AL28") (pintype "bidirectional"))
      (node (ref "R360") (pin "2") (pinfunction "2_2") (pintype "passive"))
    )
    (net (code "32") (name "/HA2_HA12_N") (class "Default")
      (node (ref "R525") (pin "2") (pinfunction "2_2") (pintype "passive"))
    )
    (net (code "33") (name "/HA2_HA12_P") (class "Default")
      (node (ref "R529") (pin "2") (pinfunction "2_2") (pintype "passive"))
    )
    (net (code "34") (name "/HA2_HA13_N") (class "Default")
      (node (ref "R533") (pin "2") (pinfunction "2_2") (pintype "passive"))
    )
    (net (code "35") (name "/HA2_HA13_P") (class "Default")
      (node (ref "R537") (pin "2") (pinfunction "2_2") (pintype "passive"))
    )
    (net (code "36") (name "/HA02_N") (class "Default")
      (node (ref "IC2") (pin "AP31") (pinfunction "IO_L10N_T1_12_AP31") (pintype "bidirectional"))
      (node (ref "R364") (pin "2") (pinfunction "2_2") (pintype "passive"))
    )
    (net (code "37") (name "/HA02_P") (class "Default")
      (node (ref "IC2") (pin "AN31") (pinfunction "IO_L10P_T1_12_AN31") (pintype "bidirectional"))
      (node (ref "R368") (pin "2") (pinfunction "2_2") (pintype "passive"))
    )
    (net (code "38") (name "/HA03_N") (class "Default")
      (node (ref "IC2") (pin "AN26") (pinfunction "IO_L21N_T3_DQS_12_AN26") (pintype "bidirectional"))
      (node (ref "R372") (pin "2") (pinfunction "2_2") (pintype "passive"))
    )
    (net (code "39") (name "/HA03_P") (class "Default")
      (node (ref "IC2") (pin "AM26") (pinfunction "IO_L21P_T3_DQS_12_AM26") (pintype "bidirectional"))
      (node (ref "R376") (pin "2") (pinfunction "2_2") (pintype "passive"))
    )
    (net (code "40") (name "/HA04_N") (class "Default")
      (node (ref "IC2") (pin "AK25") (pinfunction "IO_L19N_T3_VREF_12_AK25") (pintype "bidirectional"))
      (node (ref "R386") (pin "2") (pinfunction "2_2") (pintype "passive"))
    )
    (net (code "41") (name "/HA04_P") (class "Default")
      (node (ref "IC2") (pin "AJ25") (pinfunction "IO_L19P_T3_12_AJ25") (pintype "bidirectional"))
      (node (ref "R390") (pin "2") (pinfunction "2_2") (pintype "passive"))
    )
    (net (code "42") (name "/HA05_N") (class "Default")
      (node (ref "IC2") (pin "AM25") (pinfunction "IO_L23N_T3_12_AM25") (pintype "bidirectional"))
      (node (ref "R438") (pin "2") (pinfunction "2_2") (pintype "passive"))
    )
    (net (code "43") (name "/HA05_P") (class "Default")
      (node (ref "IC2") (pin "AL25") (pinfunction "IO_L23P_T3_12_AL25") (pintype "bidirectional"))
      (node (ref "R448") (pin "2") (pinfunction "2_2") (pintype "passive"))
    )
    (net (code "44") (name "/HA06_N") (class "Default")
      (node (ref "IC2") (pin "AM32") (pinfunction "IO_L6N_T0_VREF_12_AM32") (pintype "bidirectional"))
      (node (ref "R476") (pin "2") (pinfunction "2_2") (pintype "passive"))
    )
    (net (code "45") (name "/HA06_P") (class "Default")
      (node (ref "IC2") (pin "AL32") (pinfunction "IO_L6P_T0_12_AL32") (pintype "bidirectional"))
      (node (ref "R480") (pin "2") (pinfunction "2_2") (pintype "passive"))
    )
    (net (code "46") (name "/HA07_N") (class "Default")
      (node (ref "IC2") (pin "AN32") (pinfunction "IO_L8N_T1_12_AN32") (pintype "bidirectional"))
      (node (ref "R484") (pin "2") (pinfunction "2_2") (pintype "passive"))
    )
    (net (code "47") (name "/HA07_P") (class "Default")
      (node (ref "IC2") (pin "AM31") (pinfunction "IO_L8P_T1_12_AM31") (pintype "bidirectional"))
      (node (ref "R488") (pin "2") (pinfunction "2_2") (pintype "passive"))
    )
    (net (code "48") (name "/HA08_N") (class "Default")
      (node (ref "IC2") (pin "AN27") (pinfunction "IO_L22N_T3_12_AN27") (pintype "bidirectional"))
      (node (ref "R492") (pin "2") (pinfunction "2_2") (pintype "passive"))
    )
    (net (code "49") (name "/HA08_P") (class "Default")
      (node (ref "IC2") (pin "AM27") (pinfunction "IO_L22P_T3_12_AM27") (pintype "bidirectional"))
      (node (ref "R496") (pin "2") (pinfunction "2_2") (pintype "passive"))
    )
    (net (code "50") (name "/HA09_N") (class "Default")
      (node (ref "IC2") (pin "AK26") (pinfunction "IO_L20N_T3_12_AK26") (pintype "bidirectional"))
      (node (ref "R500") (pin "2") (pinfunction "2_2") (pintype "passive"))
    )
    (net (code "51") (name "/HA09_P") (class "Default")
      (node (ref "IC2") (pin "AJ26") (pinfunction "IO_L20P_T3_12_AJ26") (pintype "bidirectional"))
      (node (ref "R504") (pin "2") (pinfunction "2_2") (pintype "passive"))
    )
    (net (code "52") (name "/HA10_N") (class "Default")
      (node (ref "IC2") (pin "AP26") (pinfunction "IO_L24N_T3_12_AP26") (pintype "bidirectional"))
      (node (ref "R508") (pin "2") (pinfunction "2_2") (pintype "passive"))
    )
    (net (code "53") (name "/HA10_P") (class "Default")
      (node (ref "IC2") (pin "AP25") (pinfunction "IO_L24P_T3_12_AP25") (pintype "bidirectional"))
      (node (ref "R512") (pin "2") (pinfunction "2_2") (pintype "passive"))
    )
    (net (code "54") (name "/HA11_N") (class "Default")
      (node (ref "IC2") (pin "AL33") (pinfunction "IO_L4N_T0_12_AL33") (pintype "bidirectional"))
    )
    (net (code "55") (name "/HA11_P") (class "Default")
      (node (ref "IC2") (pin "AK33") (pinfunction "IO_L4P_T0_12_AK33") (pintype "bidirectional"))
    )
    (net (code "56") (name "/HA12_N") (class "Default")
      (node (ref "IC2") (pin "AN29") (pinfunction "IO_L16N_T2_12_AN29") (pintype "bidirectional"))
      (node (ref "R524") (pin "2") (pinfunction "2_2") (pintype "passive"))
      (node (ref "R525") (pin "1") (pinfunction "1_1") (pintype "passive"))
    )
    (net (code "57") (name "/HA12_P") (class "Default")
      (node (ref "IC2") (pin "AM29") (pinfunction "IO_L16P_T2_12_AM29") (pintype "bidirectional"))
      (node (ref "R528") (pin "2") (pinfunction "2_2") (pintype "passive"))
      (node (ref "R529") (pin "1") (pinfunction "1_1") (pintype "passive"))
    )
    (net (code "58") (name "/HA13_N") (class "Default")
      (node (ref "IC2") (pin "AP28") (pinfunction "IO_L17N_T2_12_AP28") (pintype "bidirectional"))
      (node (ref "R532") (pin "2") (pinfunction "2_2") (pintype "passive"))
      (node (ref "R533") (pin "1") (pinfunction "1_1") (pintype "passive"))
    )
    (net (code "59") (name "/HA13_P") (class "Default")
      (node (ref "IC2") (pin "AN28") (pinfunction "IO_L17P_T2_12_AN28") (pintype "bidirectional"))
      (node (ref "R536") (pin "2") (pinfunction "2_2") (pintype "passive"))
      (node (ref "R537") (pin "1") (pinfunction "1_1") (pintype "passive"))
    )
    (net (code "60") (name "/HA14_N") (class "Default")
      (node (ref "IC2") (pin "AP34") (pinfunction "IO_L3N_T0_DQS_12_AP34") (pintype "bidirectional"))
    )
    (net (code "61") (name "/HA14_P") (class "Default")
      (node (ref "IC2") (pin "AN34") (pinfunction "IO_L3P_T0_DQS_12_AN34") (pintype "bidirectional"))
    )
    (net (code "62") (name "/HA15_N") (class "Default")
      (node (ref "IC2") (pin "AK30") (pinfunction "IO_L11N_T1_SRCC_12_AK30") (pintype "bidirectional"))
    )
    (net (code "63") (name "/HA15_P") (class "Default")
      (node (ref "IC2") (pin "AJ29") (pinfunction "IO_L11P_T1_SRCC_12_AJ29") (pintype "bidirectional"))
    )
    (net (code "64") (name "/HA16_N") (class "Default")
      (node (ref "IC2") (pin "AL27") (pinfunction "IO_L18N_T2_12_AL27") (pintype "bidirectional"))
    )
    (net (code "65") (name "/HA16_P") (class "Default")
      (node (ref "IC2") (pin "AK27") (pinfunction "IO_L18P_T2_12_AK27") (pintype "bidirectional"))
    )
    (net (code "66") (name "/HA17_CC_N") (class "Default")
      (node (ref "IC2") (pin "AK28") (pinfunction "IO_L14N_T2_SRCC_12_AK28") (pintype "bidirectional"))
    )
    (net (code "67") (name "/HA17_CC_P") (class "Default")
      (node (ref "IC2") (pin "AJ28") (pinfunction "IO_L14P_T2_SRCC_12_AJ28") (pintype "bidirectional"))
    )
    (net (code "68") (name "/HA18_N") (class "Default")
      (node (ref "IC2") (pin "AP33") (pinfunction "IO_L5N_T0_12_AP33") (pintype "bidirectional"))
      (node (ref "R215") (pin "2") (pinfunction "2_2") (pintype "passive"))
    )
    (net (code "69") (name "/HA18_P") (class "Default")
      (node (ref "IC2") (pin "AN33") (pinfunction "IO_L5P_T0_12_AN33") (pintype "bidirectional"))
      (node (ref "R249") (pin "2") (pinfunction "2_2") (pintype "passive"))
    )
    (net (code "70") (name "/HA19_N") (class "Default")
      (node (ref "IC2") (pin "AK31") (pinfunction "IO_L9N_T1_DQS_12_AK31") (pintype "bidirectional"))
    )
    (net (code "71") (name "/HA19_P") (class "Default")
      (node (ref "IC2") (pin "AJ30") (pinfunction "IO_L9P_T1_DQS_12_AJ30") (pintype "bidirectional"))
    )
    (net (code "72") (name "/HA20_N") (class "Default")
      (node (ref "IC2") (pin "AK32") (pinfunction "IO_L7N_T1_12_AK32") (pintype "bidirectional"))
    )
    (net (code "73") (name "/HA20_P") (class "Default")
      (node (ref "IC2") (pin "AJ31") (pinfunction "IO_L7P_T1_12_AJ31") (pintype "bidirectional"))
    )
    (net (code "74") (name "/HA21_N") (class "Default")
      (node (ref "IC2") (pin "AP30") (pinfunction "IO_L15N_T2_DQS_12_AP30") (pintype "bidirectional"))
      (node (ref "R516") (pin "2") (pinfunction "2_2") (pintype "passive"))
    )
    (net (code "75") (name "/HA21_P") (class "Default")
      (node (ref "IC2") (pin "AP29") (pinfunction "IO_L15P_T2_DQS_12_AP29") (pintype "bidirectional"))
      (node (ref "R520") (pin "2") (pinfunction "2_2") (pintype "passive"))
    )
    (net (code "76") (name "/HA22_N") (class "Default")
      (node (ref "IC2") (pin "AM34") (pinfunction "IO_L1N_T0_12_AM34") (pintype "bidirectional"))
    )
    (net (code "77") (name "/HA22_P") (class "Default")
      (node (ref "IC2") (pin "AL34") (pinfunction "IO_L1P_T0_12_AL34") (pintype "bidirectional"))
    )
    (net (code "78") (name "/HA23_N") (class "Default")
      (node (ref "IC2") (pin "AJ34") (pinfunction "IO_L2N_T0_12_AJ34") (pintype "bidirectional"))
    )
    (net (code "79") (name "/HA23_P") (class "Default")
      (node (ref "IC2") (pin "AJ33") (pinfunction "IO_L2P_T0_12_AJ33") (pintype "bidirectional"))
    )
    (net (code "80") (name "/HB00_CC_N") (class "Default")
      (node (ref "IC2") (pin "T29") (pinfunction "IO_L11N_T1_SRCC_15_T29") (pintype "bidirectional"))
      (node (ref "R216") (pin "2") (pinfunction "2_2") (pintype "passive"))
      (node (ref "R243") (pin "1") (pinfunction "1_1") (pintype "passive"))
    )
    (net (code "81") (name "/HB00_CC_P") (class "Default")
      (node (ref "IC2") (pin "U29") (pinfunction "IO_L11P_T1_SRCC_15_U29") (pintype "bidirectional"))
      (node (ref "R250") (pin "2") (pinfunction "2_2") (pintype "passive"))
      (node (ref "R251") (pin "1") (pinfunction "1_1") (pintype "passive"))
    )
    (net (code "82") (name "/HB01_N") (class "Default")
      (node (ref "IC2") (pin "M27") (pinfunction "IO_L2N_T0_AD8N_15_M27") (pintype "bidirectional"))
      (node (ref "R358") (pin "2") (pinfunction "2_2") (pintype "passive"))
      (node (ref "R359") (pin "1") (pinfunction "1_1") (pintype "passive"))
    )
    (net (code "83") (name "/HB01_P") (class "Default")
      (node (ref "IC2") (pin "N26") (pinfunction "IO_L2P_T0_AD8P_15_N26") (pintype "bidirectional"))
      (node (ref "R362") (pin "2") (pinfunction "2_2") (pintype "passive"))
      (node (ref "R363") (pin "1") (pinfunction "1_1") (pintype "passive"))
    )
    (net (code "84") (name "/HB2_HB00_CC_N") (class "Default")
      (node (ref "R243") (pin "2") (pinfunction "2_2") (pintype "passive"))
    )
    (net (code "85") (name "/HB2_HB00_CC_P") (class "Default")
      (node (ref "R251") (pin "2") (pinfunction "2_2") (pintype "passive"))
    )
    (net (code "86") (name "/HB2_HB01_N") (class "Default")
      (node (ref "R359") (pin "2") (pinfunction "2_2") (pintype "passive"))
    )
    (net (code "87") (name "/HB2_HB01_P") (class "Default")
      (node (ref "R363") (pin "2") (pinfunction "2_2") (pintype "passive"))
    )
    (net (code "88") (name "/HB2_HB03_N") (class "Default")
      (node (ref "R375") (pin "2") (pinfunction "2_2") (pintype "passive"))
    )
    (net (code "89") (name "/HB2_HB03_P") (class "Default")
      (node (ref "R385") (pin "2") (pinfunction "2_2") (pintype "passive"))
    )
    (net (code "90") (name "/HB2_HB05_N") (class "Default")
      (node (ref "R445") (pin "2") (pinfunction "2_2") (pintype "passive"))
    )
    (net (code "91") (name "/HB2_HB05_P") (class "Default")
      (node (ref "R475") (pin "2") (pinfunction "2_2") (pintype "passive"))
    )
    (net (code "92") (name "/HB2_HB06_CC_N") (class "Default")
      (node (ref "R479") (pin "2") (pinfunction "2_2") (pintype "passive"))
    )
    (net (code "93") (name "/HB2_HB06_CC_P") (class "Default")
      (node (ref "R483") (pin "2") (pinfunction "2_2") (pintype "passive"))
    )
    (net (code "94") (name "/HB2_HB15_N") (class "Default")
      (node (ref "R545") (pin "2") (pinfunction "2_2") (pintype "passive"))
    )
    (net (code "95") (name "/HB2_HB15_P") (class "Default")
      (node (ref "R547") (pin "2") (pinfunction "2_2") (pintype "passive"))
    )
    (net (code "96") (name "/HB2_HB18_N") (class "Default")
      (node (ref "R527") (pin "2") (pinfunction "2_2") (pintype "passive"))
    )
    (net (code "97") (name "/HB2_HB18_P") (class "Default")
      (node (ref "R531") (pin "2") (pinfunction "2_2") (pintype "passive"))
    )
    (net (code "98") (name "/HB02_N") (class "Default")
      (node (ref "IC2") (pin "M34") (pinfunction "IO_L22N_T3_A16_15_M34") (pintype "bidirectional"))
      (node (ref "R366") (pin "2") (pinfunction "2_2") (pintype "passive"))
    )
    (net (code "99") (name "/HB02_P") (class "Default")
      (node (ref "IC2") (pin "N34") (pinfunction "IO_L22P_T3_A17_15_N34") (pintype "bidirectional"))
      (node (ref "R370") (pin "2") (pinfunction "2_2") (pintype "passive"))
    )
    (net (code "100") (name "/HB03_N") (class "Default")
      (node (ref "IC2") (pin "T34") (pinfunction "IO_L23N_T3_FWE_B_15_T34") (pintype "bidirectional"))
      (node (ref "R374") (pin "2") (pinfunction "2_2") (pintype "passive"))
      (node (ref "R375") (pin "1") (pinfunction "1_1") (pintype "passive"))
    )
    (net (code "101") (name "/HB03_P") (class "Default")
      (node (ref "IC2") (pin "U34") (pinfunction "IO_L23P_T3_FOE_B_15_U34") (pintype "bidirectional"))
      (node (ref "R378") (pin "2") (pinfunction "2_2") (pintype "passive"))
      (node (ref "R385") (pin "1") (pinfunction "1_1") (pintype "passive"))
    )
    (net (code "102") (name "/HB04_N") (class "Default")
      (node (ref "IC2") (pin "U27") (pinfunction "IO_L5N_T0_AD9N_15_U27") (pintype "bidirectional"))
    )
    (net (code "103") (name "/HB04_P") (class "Default")
      (node (ref "IC2") (pin "U26") (pinfunction "IO_L5P_T0_AD9P_15_U26") (pintype "bidirectional"))
    )
    (net (code "104") (name "/HB05_N") (class "Default")
      (node (ref "IC2") (pin "P34") (pinfunction "IO_L24N_T3_RS0_15_P34") (pintype "bidirectional"))
      (node (ref "R442") (pin "2") (pinfunction "2_2") (pintype "passive"))
      (node (ref "R445") (pin "1") (pinfunction "1_1") (pintype "passive"))
    )
    (net (code "105") (name "/HB05_P") (class "Default")
      (node (ref "IC2") (pin "P33") (pinfunction "IO_L24P_T3_RS1_15_P33") (pintype "bidirectional"))
      (node (ref "R450") (pin "2") (pinfunction "2_2") (pintype "passive"))
      (node (ref "R475") (pin "1") (pinfunction "1_1") (pintype "passive"))
    )
    (net (code "106") (name "/HB06_CC_N") (class "Default")
      (node (ref "IC2") (pin "P30") (pinfunction "IO_L13N_T2_MRCC_15_P30") (pintype "bidirectional"))
      (node (ref "R478") (pin "2") (pinfunction "2_2") (pintype "passive"))
      (node (ref "R479") (pin "1") (pinfunction "1_1") (pintype "passive"))
      (node (ref "R569") (pin "2") (pinfunction "2_2") (pintype "passive"))
    )
    (net (code "107") (name "/HB06_CC_P") (class "Default")
      (node (ref "IC2") (pin "R30") (pinfunction "IO_L13P_T2_MRCC_15_R30") (pintype "bidirectional"))
      (node (ref "R482") (pin "2") (pinfunction "2_2") (pintype "passive"))
      (node (ref "R483") (pin "1") (pinfunction "1_1") (pintype "passive"))
      (node (ref "R570") (pin "2") (pinfunction "2_2") (pintype "passive"))
    )
    (net (code "108") (name "/HB07_N") (class "Default")
      (node (ref "IC2") (pin "N24") (pinfunction "IO_L4N_T0_15_N24") (pintype "bidirectional"))
      (node (ref "R486") (pin "2") (pinfunction "2_2") (pintype "passive"))
    )
    (net (code "109") (name "/HB07_P") (class "Default")
      (node (ref "IC2") (pin "P24") (pinfunction "IO_L4P_T0_15_P24") (pintype "bidirectional"))
      (node (ref "R490") (pin "2") (pinfunction "2_2") (pintype "passive"))
    )
    (net (code "110") (name "/HB08_N") (class "Default")
      (node (ref "IC2") (pin "P26") (pinfunction "IO_L1N_T0_AD0N_15_P26") (pintype "bidirectional"))
      (node (ref "R494") (pin "2") (pinfunction "2_2") (pintype "passive"))
    )
    (net (code "111") (name "/HB08_P") (class "Default")
      (node (ref "IC2") (pin "R26") (pinfunction "IO_L1P_T0_AD0P_15_R26") (pintype "bidirectional"))
      (node (ref "R498") (pin "2") (pinfunction "2_2") (pintype "passive"))
    )
    (net (code "112") (name "/HB09_N") (class "Default")
      (node (ref "IC2") (pin "R28") (pinfunction "IO_L9N_T1_DQS_AD3N_15_R28") (pintype "bidirectional"))
      (node (ref "R502") (pin "2") (pinfunction "2_2") (pintype "passive"))
    )
    (net (code "113") (name "/HB09_P") (class "Default")
      (node (ref "IC2") (pin "T28") (pinfunction "IO_L9P_T1_DQS_AD3P_15_T28") (pintype "bidirectional"))
      (node (ref "R506") (pin "2") (pinfunction "2_2") (pintype "passive"))
    )
    (net (code "114") (name "/HB10_N") (class "Default")
      (node (ref "IC2") (pin "T25") (pinfunction "IO_L3N_T0_DQS_AD1N_15_T25") (pintype "bidirectional"))
      (node (ref "R510") (pin "2") (pinfunction "2_2") (pintype "passive"))
    )
    (net (code "115") (name "/HB10_P") (class "Default")
      (node (ref "IC2") (pin "U25") (pinfunction "IO_L3P_T0_DQS_AD1P_15_U25") (pintype "bidirectional"))
      (node (ref "R514") (pin "2") (pinfunction "2_2") (pintype "passive"))
    )
    (net (code "116") (name "/HB11_N") (class "Default")
      (node (ref "IC2") (pin "R27") (pinfunction "IO_L7N_T1_AD2N_15_R27") (pintype "bidirectional"))
      (node (ref "R518") (pin "2") (pinfunction "2_2") (pintype "passive"))
    )
    (net (code "117") (name "/HB11_P") (class "Default")
      (node (ref "IC2") (pin "T27") (pinfunction "IO_L7P_T1_AD2P_15_T27") (pintype "bidirectional"))
      (node (ref "R522") (pin "2") (pinfunction "2_2") (pintype "passive"))
    )
    (net (code "118") (name "/HB12_N") (class "Default")
      (node (ref "IC2") (pin "M32") (pinfunction "IO_L17N_T2_A25_15_M32") (pintype "bidirectional"))
    )
    (net (code "119") (name "/HB12_P") (class "Default")
      (node (ref "IC2") (pin "N31") (pinfunction "IO_L17P_T2_A26_15_N31") (pintype "bidirectional"))
    )
    (net (code "120") (name "/HB13_N") (class "Default")
      (node (ref "IC2") (pin "N28") (pinfunction "IO_L8N_T1_AD10N_15_N28") (pintype "bidirectional"))
      (node (ref "R535") (pin "2") (pinfunction "2_2") (pintype "passive"))
    )
    (net (code "121") (name "/HB13_P") (class "Default")
      (node (ref "IC2") (pin "N27") (pinfunction "IO_L8P_T1_AD10P_15_N27") (pintype "bidirectional"))
      (node (ref "R539") (pin "2") (pinfunction "2_2") (pintype "passive"))
    )
    (net (code "122") (name "/HB14_N") (class "Default")
      (node (ref "IC2") (pin "P31") (pinfunction "IO_L16N_T2_A27_15_P31") (pintype "bidirectional"))
    )
    (net (code "123") (name "/HB14_P") (class "Default")
      (node (ref "IC2") (pin "R31") (pinfunction "IO_L16P_T2_A28_15_R31") (pintype "bidirectional"))
    )
    (net (code "124") (name "/HB15_N") (class "Default")
      (node (ref "IC2") (pin "T30") (pinfunction "IO_L14N_T2_SRCC_15_T30") (pintype "bidirectional"))
      (node (ref "R544") (pin "2") (pinfunction "2_2") (pintype "passive"))
      (node (ref "R545") (pin "1") (pinfunction "1_1") (pintype "passive"))
    )
    (net (code "125") (name "/HB15_P") (class "Default")
      (node (ref "IC2") (pin "U30") (pinfunction "IO_L14P_T2_SRCC_15_U30") (pintype "bidirectional"))
      (node (ref "R546") (pin "2") (pinfunction "2_2") (pintype "passive"))
      (node (ref "R547") (pin "1") (pinfunction "1_1") (pintype "passive"))
    )
    (net (code "126") (name "/HB16_N") (class "Default")
      (node (ref "IC2") (pin "U32") (pinfunction "IO_L18N_T2_A23_15_U32") (pintype "bidirectional"))
    )
    (net (code "127") (name "/HB16_P") (class "Default")
      (node (ref "IC2") (pin "U31") (pinfunction "IO_L18P_T2_A24_15_U31") (pintype "bidirectional"))
    )
    (net (code "128") (name "/HB17_CC_N") (class "Default")
      (node (ref "IC2") (pin "P29") (pinfunction "IO_L12N_T1_MRCC_15_P29") (pintype "bidirectional"))
      (node (ref "R548") (pin "2") (pinfunction "2_2") (pintype "passive"))
    )
    (net (code "129") (name "/HB17_CC_P") (class "Default")
      (node (ref "IC2") (pin "P28") (pinfunction "IO_L12P_T1_MRCC_15_P28") (pintype "bidirectional"))
      (node (ref "R549") (pin "2") (pinfunction "2_2") (pintype "passive"))
    )
    (net (code "130") (name "/HB18_N") (class "Default")
      (node (ref "IC2") (pin "M29") (pinfunction "IO_L10N_T1_AD11N_15_M29") (pintype "bidirectional"))
      (node (ref "R526") (pin "2") (pinfunction "2_2") (pintype "passive"))
      (node (ref "R527") (pin "1") (pinfunction "1_1") (pintype "passive"))
    )
    (net (code "131") (name "/HB18_P") (class "Default")
      (node (ref "IC2") (pin "N29") (pinfunction "IO_L10P_T1_AD11P_15_N29") (pintype "bidirectional"))
      (node (ref "R530") (pin "2") (pinfunction "2_2") (pintype "passive"))
      (node (ref "R531") (pin "1") (pinfunction "1_1") (pintype "passive"))
    )
    (net (code "132") (name "/HB19_N") (class "Default")
      (node (ref "IC2") (pin "M31") (pinfunction "IO_L15N_T2_DQS_ADV_B_15_M31") (pintype "bidirectional"))
    )
    (net (code "133") (name "/HB19_P") (class "Default")
      (node (ref "IC2") (pin "M30") (pinfunction "IO_L15P_T2_DQS_15_M30") (pintype "bidirectional"))
    )
    (net (code "134") (name "/HB20_N") (class "Default")
      (node (ref "IC2") (pin "N33") (pinfunction "IO_L20N_T3_A19_15_N33") (pintype "bidirectional"))
    )
    (net (code "135") (name "/HB20_P") (class "Default")
      (node (ref "IC2") (pin "N32") (pinfunction "IO_L20P_T3_A20_15_N32") (pintype "bidirectional"))
    )
    (net (code "136") (name "/HB21_N") (class "Default")
      (node (ref "IC2") (pin "R33") (pinfunction "IO_L21N_T3_DQS_A18_15_R33") (pintype "bidirectional"))
      (node (ref "R534") (pin "2") (pinfunction "2_2") (pintype "passive"))
    )
    (net (code "137") (name "/HB21_P") (class "Default")
      (node (ref "IC2") (pin "T33") (pinfunction "IO_L21P_T3_DQS_15_T33") (pintype "bidirectional"))
      (node (ref "R538") (pin "2") (pinfunction "2_2") (pintype "passive"))
    )
    (net (code "138") (name "/I2C_RST") (class "Default")
      (node (ref "IC2") (pin "AD31") (pinfunction "IO_L7P_T1_13_AD31") (pintype "bidirectional"))
    )
    (net (code "139") (name "/LA2_LA00_CC_N") (class "Default")
      (node (ref "IC2") (pin "AF28") (pinfunction "IO_L14N_T2_SRCC_13_AF28") (pintype "bidirectional"))
    )
    (net (code "140") (name "/LA2_LA00_CC_P") (class "Default")
      (node (ref "IC2") (pin "AE28") (pinfunction "IO_L14P_T2_SRCC_13_AE28") (pintype "bidirectional"))
    )
    (net (code "141") (name "/LA2_LA01_CC_N") (class "Default")
      (node (ref "IC2") (pin "AF30") (pinfunction "IO_L11N_T1_SRCC_13_AF30") (pintype "bidirectional"))
    )
    (net (code "142") (name "/LA2_LA01_CC_P") (class "Default")
      (node (ref "IC2") (pin "AF29") (pinfunction "IO_L11P_T1_SRCC_13_AF29") (pintype "bidirectional"))
    )
    (net (code "143") (name "/LA2_LA02_N") (class "Default")
      (node (ref "IC2") (pin "AH31") (pinfunction "IO_L10N_T1_13_AH31") (pintype "bidirectional"))
    )
    (net (code "144") (name "/LA2_LA02_P") (class "Default")
      (node (ref "IC2") (pin "AG31") (pinfunction "IO_L10P_T1_13_AG31") (pintype "bidirectional"))
    )
    (net (code "145") (name "/LA2_LA03_N") (class "Default")
      (node (ref "IC2") (pin "AH24") (pinfunction "IO_L21N_T3_DQS_13_AH24") (pintype "bidirectional"))
    )
    (net (code "146") (name "/LA2_LA03_P") (class "Default")
      (node (ref "IC2") (pin "AG24") (pinfunction "IO_L21P_T3_DQS_13_AG24") (pintype "bidirectional"))
    )
    (net (code "147") (name "/LA2_LA04_N") (class "Default")
      (node (ref "IC2") (pin "AC27") (pinfunction "IO_L16N_T2_13_AC27") (pintype "bidirectional"))
    )
    (net (code "148") (name "/LA2_LA04_P") (class "Default")
      (node (ref "IC2") (pin "AC26") (pinfunction "IO_L16P_T2_13_AC26") (pintype "bidirectional"))
    )
    (net (code "149") (name "/LA2_LA05_N") (class "Default")
      (node (ref "IC2") (pin "AH34") (pinfunction "IO_L3N_T0_DQS_13_AH34") (pintype "bidirectional"))
    )
    (net (code "150") (name "/LA2_LA05_P") (class "Default")
      (node (ref "IC2") (pin "AH33") (pinfunction "IO_L3P_T0_DQS_13_AH33") (pintype "bidirectional"))
    )
    (net (code "151") (name "/LA2_LA06_N") (class "Default")
      (node (ref "IC2") (pin "AF23") (pinfunction "IO_L20N_T3_13_AF23") (pintype "bidirectional"))
    )
    (net (code "152") (name "/LA2_LA06_P") (class "Default")
      (node (ref "IC2") (pin "AE23") (pinfunction "IO_L20P_T3_13_AE23") (pintype "bidirectional"))
    )
    (net (code "153") (name "/LA2_LA07_N") (class "Default")
      (node (ref "IC2") (pin "AH27") (pinfunction "IO_L17N_T2_13_AH27") (pintype "bidirectional"))
    )
    (net (code "154") (name "/LA2_LA07_P") (class "Default")
      (node (ref "IC2") (pin "AG27") (pinfunction "IO_L17P_T2_13_AG27") (pintype "bidirectional"))
    )
    (net (code "155") (name "/LA2_LA08_N") (class "Default")
      (node (ref "IC2") (pin "AE25") (pinfunction "IO_L24N_T3_13_AE25") (pintype "bidirectional"))
    )
    (net (code "156") (name "/LA2_LA08_P") (class "Default")
      (node (ref "IC2") (pin "AD25") (pinfunction "IO_L24P_T3_13_AD25") (pintype "bidirectional"))
    )
    (net (code "157") (name "/LA2_LA09_N") (class "Default")
      (node (ref "IC2") (pin "AG25") (pinfunction "IO_L23N_T3_13_AG25") (pintype "bidirectional"))
    )
    (net (code "158") (name "/LA2_LA09_P") (class "Default")
      (node (ref "IC2") (pin "AF25") (pinfunction "IO_L23P_T3_13_AF25") (pintype "bidirectional"))
    )
    (net (code "159") (name "/LA2_LA10_N") (class "Default")
      (node (ref "IC2") (pin "AH32") (pinfunction "IO_L5N_T0_13_AH32") (pintype "bidirectional"))
    )
    (net (code "160") (name "/LA2_LA10_P") (class "Default")
      (node (ref "IC2") (pin "AG32") (pinfunction "IO_L5P_T0_13_AG32") (pintype "bidirectional"))
    )
    (net (code "161") (name "/LA2_LA11_N") (class "Default")
      (node (ref "IC2") (pin "AE30") (pinfunction "IO_L8N_T1_13_AE30") (pintype "bidirectional"))
    )
    (net (code "162") (name "/LA2_LA11_P") (class "Default")
      (node (ref "IC2") (pin "AD30") (pinfunction "IO_L8P_T1_13_AD30") (pintype "bidirectional"))
    )
    (net (code "163") (name "/LA2_LA12_N") (class "Default")
      (node (ref "IC2") (pin "AF27") (pinfunction "IO_L18N_T2_13_AF27") (pintype "bidirectional"))
    )
    (net (code "164") (name "/LA2_LA12_P") (class "Default")
      (node (ref "IC2") (pin "AE27") (pinfunction "IO_L18P_T2_13_AE27") (pintype "bidirectional"))
    )
    (net (code "165") (name "/LA2_LA13_N") (class "Default")
      (node (ref "IC2") (pin "AG34") (pinfunction "IO_L1N_T0_13_AG34") (pintype "bidirectional"))
    )
    (net (code "166") (name "/LA2_LA13_P") (class "Default")
      (node (ref "IC2") (pin "AF34") (pinfunction "IO_L1P_T0_13_AF34") (pintype "bidirectional"))
    )
    (net (code "167") (name "/LA2_LA14_N") (class "Default")
      (node (ref "IC2") (pin "AF33") (pinfunction "IO_L4N_T0_13_AF33") (pintype "bidirectional"))
    )
    (net (code "168") (name "/LA2_LA14_P") (class "Default")
      (node (ref "IC2") (pin "AE33") (pinfunction "IO_L4P_T0_13_AE33") (pintype "bidirectional"))
    )
    (net (code "169") (name "/LA2_LA15_N") (class "Default")
      (node (ref "IC2") (pin "AD29") (pinfunction "IO_L9N_T1_DQS_13_AD29") (pintype "bidirectional"))
    )
    (net (code "170") (name "/LA2_LA15_P") (class "Default")
      (node (ref "IC2") (pin "AD28") (pinfunction "IO_L9P_T1_DQS_13_AD28") (pintype "bidirectional"))
    )
    (net (code "171") (name "/LA2_LA16_N") (class "Default")
      (node (ref "IC2") (pin "AD34") (pinfunction "IO_L2N_T0_13_AD34") (pintype "bidirectional"))
    )
    (net (code "172") (name "/LA2_LA16_P") (class "Default")
      (node (ref "IC2") (pin "AD33") (pinfunction "IO_L2P_T0_13_AD33") (pintype "bidirectional"))
    )
    (net (code "173") (name "/LA2_LA17_CC_N") (class "Default")
      (node (ref "IC2") (pin "AB32") (pinfunction "IO_L14N_T2_SRCC_14_AB32") (pintype "bidirectional"))
    )
    (net (code "174") (name "/LA2_LA17_CC_P") (class "Default")
      (node (ref "IC2") (pin "AB31") (pinfunction "IO_L14P_T2_SRCC_14_AB31") (pintype "bidirectional"))
    )
    (net (code "175") (name "/LA2_LA18_CC_N") (class "Default")
      (node (ref "IC2") (pin "W31") (pinfunction "IO_L11N_T1_SRCC_14_W31") (pintype "bidirectional"))
    )
    (net (code "176") (name "/LA2_LA18_CC_P") (class "Default")
      (node (ref "IC2") (pin "W30") (pinfunction "IO_L11P_T1_SRCC_14_W30") (pintype "bidirectional"))
    )
    (net (code "177") (name "/LA2_LA19_N") (class "Default")
      (node (ref "IC2") (pin "AB27") (pinfunction "IO_L21N_T3_DQS_A06_D22_14_AB27") (pintype "bidirectional"))
    )
    (net (code "178") (name "/LA2_LA19_P") (class "Default")
      (node (ref "IC2") (pin "AB26") (pinfunction "IO_L21P_T3_DQS_14_AB26") (pintype "bidirectional"))
    )
    (net (code "179") (name "/LA2_LA20_N") (class "Default")
      (node (ref "IC2") (pin "AB25") (pinfunction "IO_L24N_T3_A00_D16_14_AB25") (pintype "bidirectional"))
    )
    (net (code "180") (name "/LA2_LA20_P") (class "Default")
      (node (ref "IC2") (pin "AB24") (pinfunction "IO_L24P_T3_A01_D17_14_AB24") (pintype "bidirectional"))
    )
    (net (code "181") (name "/LA2_LA21_N") (class "Default")
      (node (ref "IC2") (pin "AA33") (pinfunction "IO_L16N_T2_A15_D31_14_AA33") (pintype "bidirectional"))
    )
    (net (code "182") (name "/LA2_LA21_P") (class "Default")
      (node (ref "IC2") (pin "AA32") (pinfunction "IO_L16P_T2_CSI_B_14_AA32") (pintype "bidirectional"))
    )
    (net (code "183") (name "/LA2_LA22_N") (class "Default")
      (node (ref "IC2") (pin "AA25") (pinfunction "IO_L23N_T3_A02_D18_14_AA25") (pintype "bidirectional"))
    )
    (net (code "184") (name "/LA2_LA22_P") (class "Default")
      (node (ref "IC2") (pin "AA24") (pinfunction "IO_L23P_T3_A03_D19_14_AA24") (pintype "bidirectional"))
    )
    (net (code "185") (name "/LA2_LA23_N") (class "Default")
      (node (ref "IC2") (pin "Y25") (pinfunction "IO_L5N_T0_D07_14_Y25") (pintype "bidirectional"))
    )
    (net (code "186") (name "/LA2_LA23_P") (class "Default")
      (node (ref "IC2") (pin "W25") (pinfunction "IO_L5P_T0_D06_14_W25") (pintype "bidirectional"))
    )
    (net (code "187") (name "/LA2_LA24_N") (class "Default")
      (node (ref "IC2") (pin "Y33") (pinfunction "IO_L10N_T1_D15_14_Y33") (pintype "bidirectional"))
    )
    (net (code "188") (name "/LA2_LA24_P") (class "Default")
      (node (ref "IC2") (pin "Y32") (pinfunction "IO_L10P_T1_D14_14_Y32") (pintype "bidirectional"))
    )
    (net (code "189") (name "/LA2_LA25_N") (class "Default")
      (node (ref "IC2") (pin "AB29") (pinfunction "IO_L22N_T3_A04_D20_14_AB29") (pintype "bidirectional"))
    )
    (net (code "190") (name "/LA2_LA25_P") (class "Default")
      (node (ref "IC2") (pin "AA29") (pinfunction "IO_L22P_T3_A05_D21_14_AA29") (pintype "bidirectional"))
    )
    (net (code "191") (name "/LA2_LA26_N") (class "Default")
      (node (ref "IC2") (pin "AC32") (pinfunction "IO_L17N_T2_A13_D29_14_AC32") (pintype "bidirectional"))
    )
    (net (code "192") (name "/LA2_LA26_P") (class "Default")
      (node (ref "IC2") (pin "AC31") (pinfunction "IO_L17P_T2_A14_D30_14_AC31") (pintype "bidirectional"))
    )
    (net (code "193") (name "/LA2_LA27_N") (class "Default")
      (node (ref "IC2") (pin "AA28") (pinfunction "IO_L20N_T3_A07_D23_14_AA28") (pintype "bidirectional"))
    )
    (net (code "194") (name "/LA2_LA27_P") (class "Default")
      (node (ref "IC2") (pin "AA27") (pinfunction "IO_L20P_T3_A08_D24_14_AA27") (pintype "bidirectional"))
    )
    (net (code "195") (name "/LA2_LA28_N") (class "Default")
      (node (ref "IC2") (pin "W29") (pinfunction "IO_L4N_T0_D05_14_W29") (pintype "bidirectional"))
    )
    (net (code "196") (name "/LA2_LA28_P") (class "Default")
      (node (ref "IC2") (pin "W28") (pinfunction "IO_L4P_T0_D04_14_W28") (pintype "bidirectional"))
    )
    (net (code "197") (name "/LA2_LA29_N") (class "Default")
      (node (ref "IC2") (pin "AC34") (pinfunction "IO_L15N_T2_DQS_DOUT_CSO_B_14_AC34") (pintype "bidirectional"))
    )
    (net (code "198") (name "/LA2_LA29_P") (class "Default")
      (node (ref "IC2") (pin "AC33") (pinfunction "IO_L15P_T2_DQS_RDWR_B_14_AC33") (pintype "bidirectional"))
    )
    (net (code "199") (name "/LA2_LA30_N") (class "Default")
      (node (ref "IC2") (pin "W34") (pinfunction "IO_L8N_T1_D12_14_W34") (pintype "bidirectional"))
    )
    (net (code "200") (name "/LA2_LA30_P") (class "Default")
      (node (ref "IC2") (pin "W33") (pinfunction "IO_L8P_T1_D11_14_W33") (pintype "bidirectional"))
    )
    (net (code "201") (name "/LA2_LA31_N") (class "Default")
      (node (ref "IC2") (pin "V32") (pinfunction "IO_L7N_T1_D10_14_V32") (pintype "bidirectional"))
    )
    (net (code "202") (name "/LA2_LA31_P") (class "Default")
      (node (ref "IC2") (pin "V31") (pinfunction "IO_L7P_T1_D09_14_V31") (pintype "bidirectional"))
    )
    (net (code "203") (name "/LA2_LA32_N") (class "Default")
      (node (ref "IC2") (pin "AB34") (pinfunction "IO_L18N_T2_A11_D27_14_AB34") (pintype "bidirectional"))
    )
    (net (code "204") (name "/LA2_LA32_P") (class "Default")
      (node (ref "IC2") (pin "AA34") (pinfunction "IO_L18P_T2_A12_D28_14_AA34") (pintype "bidirectional"))
    )
    (net (code "205") (name "/LA2_LA33_N") (class "Default")
      (node (ref "IC2") (pin "V34") (pinfunction "IO_L9N_T1_DQS_D13_14_V34") (pintype "bidirectional"))
    )
    (net (code "206") (name "/LA2_LA33_P") (class "Default")
      (node (ref "IC2") (pin "V33") (pinfunction "IO_L9P_T1_DQS_14_V33") (pintype "bidirectional"))
    )
    (net (code "207") (name "/PRI_UART_Rx") (class "Default")
      (node (ref "IC2") (pin "AG29") (pinfunction "IO_L12P_T1_MRCC_13_AG29") (pintype "bidirectional"))
      (node (ref "TP15") (pin "1") (pintype "passive"))
    )
    (net (code "208") (name "/PRI_UART_Tx") (class "Default")
      (node (ref "IC2") (pin "AG30") (pinfunction "IO_L12N_T1_MRCC_13_AG30") (pintype "bidirectional"))
      (node (ref "TP14") (pin "1") (pintype "passive"))
    )
    (net (code "209") (name "/PUDC") (class "Default")
      (node (ref "IC2") (pin "W26") (pinfunction "IO_L3P_T0_DQS_PUDC_B_14_W26") (pintype "bidirectional"))
      (node (ref "R180") (pin "1") (pinfunction "1_1") (pintype "passive"))
    )
    (net (code "210") (name "/RTM.P30_IO5_AB_B1_CC_N") (class "Default")
      (node (ref "R252") (pin "1") (pinfunction "1_1") (pintype "passive"))
    )
    (net (code "211") (name "/RTM.P30_IO5_AB_B1_CC_P") (class "Default")
      (node (ref "R360") (pin "1") (pinfunction "1_1") (pintype "passive"))
    )
    (net (code "212") (name "/RTM.P30_IO5_CD_B1_N") (class "Default")
      (node (ref "R492") (pin "1") (pinfunction "1_1") (pintype "passive"))
    )
    (net (code "213") (name "/RTM.P30_IO5_CD_B1_P") (class "Default")
      (node (ref "R496") (pin "1") (pinfunction "1_1") (pintype "passive"))
    )
    (net (code "214") (name "/RTM.P30_IO5_EF_B1_N") (class "Default")
      (node (ref "R438") (pin "1") (pinfunction "1_1") (pintype "passive"))
    )
    (net (code "215") (name "/RTM.P30_IO5_EF_B1_P") (class "Default")
      (node (ref "R448") (pin "1") (pinfunction "1_1") (pintype "passive"))
    )
    (net (code "216") (name "/RTM.P30_IO6_AB_B1_CC_N") (class "Default")
      (node (ref "R51") (pin "1") (pinfunction "1_1") (pintype "passive"))
    )
    (net (code "217") (name "/RTM.P30_IO6_AB_B1_CC_P") (class "Default")
      (node (ref "R245") (pin "1") (pinfunction "1_1") (pintype "passive"))
    )
    (net (code "218") (name "/RTM.P30_IO6_CD_B1_N") (class "Default")
      (node (ref "R532") (pin "1") (pinfunction "1_1") (pintype "passive"))
    )
    (net (code "219") (name "/RTM.P30_IO6_CD_B1_P") (class "Default")
      (node (ref "R536") (pin "1") (pinfunction "1_1") (pintype "passive"))
    )
    (net (code "220") (name "/RTM.P30_IO6_EF_B1_N") (class "Default")
      (node (ref "R386") (pin "1") (pinfunction "1_1") (pintype "passive"))
    )
    (net (code "221") (name "/RTM.P30_IO6_EF_B1_P") (class "Default")
      (node (ref "R390") (pin "1") (pinfunction "1_1") (pintype "passive"))
    )
    (net (code "222") (name "/RTM.P30_IO7_AB_B1_N") (class "Default")
      (node (ref "R524") (pin "1") (pinfunction "1_1") (pintype "passive"))
    )
    (net (code "223") (name "/RTM.P30_IO7_AB_B1_P") (class "Default")
      (node (ref "R528") (pin "1") (pinfunction "1_1") (pintype "passive"))
    )
    (net (code "224") (name "/RTM.P30_IO7_CD_B1_N") (class "Default")
      (node (ref "R500") (pin "1") (pinfunction "1_1") (pintype "passive"))
    )
    (net (code "225") (name "/RTM.P30_IO7_CD_B1_P") (class "Default")
      (node (ref "R504") (pin "1") (pinfunction "1_1") (pintype "passive"))
    )
    (net (code "226") (name "/RTM.P30_IO7_EF_B1_N") (class "Default")
      (node (ref "R476") (pin "1") (pinfunction "1_1") (pintype "passive"))
    )
    (net (code "227") (name "/RTM.P30_IO7_EF_B1_P") (class "Default")
      (node (ref "R480") (pin "1") (pinfunction "1_1") (pintype "passive"))
    )
    (net (code "228") (name "/RTM.P30_IO8_AB_B1_N") (class "Default")
      (node (ref "R508") (pin "1") (pinfunction "1_1") (pintype "passive"))
    )
    (net (code "229") (name "/RTM.P30_IO8_AB_B1_P") (class "Default")
      (node (ref "R512") (pin "1") (pinfunction "1_1") (pintype "passive"))
    )
    (net (code "230") (name "/RTM.P30_IO8_CD_B1_N") (class "Default")
      (node (ref "R516") (pin "1") (pinfunction "1_1") (pintype "passive"))
    )
    (net (code "231") (name "/RTM.P30_IO8_CD_B1_P") (class "Default")
      (node (ref "R520") (pin "1") (pinfunction "1_1") (pintype "passive"))
    )
    (net (code "232") (name "/RTM.P30_IO8_EF_B1_N") (class "Default")
      (node (ref "R215") (pin "1") (pinfunction "1_1") (pintype "passive"))
    )
    (net (code "233") (name "/RTM.P30_IO8_EF_B1_P") (class "Default")
      (node (ref "R249") (pin "1") (pinfunction "1_1") (pintype "passive"))
    )
    (net (code "234") (name "/RTM.P30_IO9_AB_B2_CC_N") (class "Default")
      (node (ref "R478") (pin "1") (pinfunction "1_1") (pintype "passive"))
    )
    (net (code "235") (name "/RTM.P30_IO9_AB_B2_CC_P") (class "Default")
      (node (ref "R482") (pin "1") (pinfunction "1_1") (pintype "passive"))
    )
    (net (code "236") (name "/RTM.P30_IO9_CD_B2_N") (class "Default")
      (node (ref "R366") (pin "1") (pinfunction "1_1") (pintype "passive"))
    )
    (net (code "237") (name "/RTM.P30_IO9_CD_B2_P") (class "Default")
      (node (ref "R370") (pin "1") (pinfunction "1_1") (pintype "passive"))
    )
    (net (code "238") (name "/RTM.P30_IO9_EF_B2_N") (class "Default")
      (node (ref "R486") (pin "1") (pinfunction "1_1") (pintype "passive"))
    )
    (net (code "239") (name "/RTM.P30_IO9_EF_B2_P") (class "Default")
      (node (ref "R490") (pin "1") (pinfunction "1_1") (pintype "passive"))
    )
    (net (code "240") (name "/RTM.P30_IO10_AB_B2_CC_N") (class "Default")
      (node (ref "R216") (pin "1") (pinfunction "1_1") (pintype "passive"))
    )
    (net (code "241") (name "/RTM.P30_IO10_AB_B2_CC_P") (class "Default")
      (node (ref "R250") (pin "1") (pinfunction "1_1") (pintype "passive"))
    )
    (net (code "242") (name "/RTM.P30_IO10_CD_B2_N") (class "Default")
      (node (ref "R502") (pin "1") (pinfunction "1_1") (pintype "passive"))
    )
    (net (code "243") (name "/RTM.P30_IO10_CD_B2_P") (class "Default")
      (node (ref "R506") (pin "1") (pinfunction "1_1") (pintype "passive"))
    )
    (net (code "244") (name "/RTM.P30_IO10_EF_B2_N") (class "Default")
      (node (ref "R494") (pin "1") (pinfunction "1_1") (pintype "passive"))
    )
    (net (code "245") (name "/RTM.P30_IO10_EF_B2_P") (class "Default")
      (node (ref "R498") (pin "1") (pinfunction "1_1") (pintype "passive"))
    )
    (net (code "246") (name "/RTM.P30_OUT0_N") (class "Default")
      (node (ref "R372") (pin "1") (pinfunction "1_1") (pintype "passive"))
    )
    (net (code "247") (name "/RTM.P30_OUT0_P") (class "Default")
      (node (ref "R376") (pin "1") (pinfunction "1_1") (pintype "passive"))
    )
    (net (code "248") (name "/RTM.P30_OUT1_N") (class "Default")
      (node (ref "R484") (pin "1") (pinfunction "1_1") (pintype "passive"))
    )
    (net (code "249") (name "/RTM.P30_OUT1_P") (class "Default")
      (node (ref "R488") (pin "1") (pinfunction "1_1") (pintype "passive"))
    )
    (net (code "250") (name "/RTM.P30_OUT2_N") (class "Default")
      (node (ref "R364") (pin "1") (pinfunction "1_1") (pintype "passive"))
    )
    (net (code "251") (name "/RTM.P30_OUT2_P") (class "Default")
      (node (ref "R368") (pin "1") (pinfunction "1_1") (pintype "passive"))
    )
    (net (code "252") (name "/RTM.P31_IO1_AB_B2_N") (class "Default")
      (node (ref "R510") (pin "1") (pinfunction "1_1") (pintype "passive"))
    )
    (net (code "253") (name "/RTM.P31_IO1_AB_B2_P") (class "Default")
      (node (ref "R514") (pin "1") (pinfunction "1_1") (pintype "passive"))
    )
    (net (code "254") (name "/RTM.P31_IO1_CD_B2_N") (class "Default")
      (node (ref "R518") (pin "1") (pinfunction "1_1") (pintype "passive"))
    )
    (net (code "255") (name "/RTM.P31_IO1_CD_B2_P") (class "Default")
      (node (ref "R522") (pin "1") (pinfunction "1_1") (pintype "passive"))
    )
    (net (code "256") (name "/RTM.P31_IO1_EF_B2_N") (class "Default")
      (node (ref "R535") (pin "1") (pinfunction "1_1") (pintype "passive"))
    )
    (net (code "257") (name "/RTM.P31_IO1_EF_B2_P") (class "Default")
      (node (ref "R539") (pin "1") (pinfunction "1_1") (pintype "passive"))
    )
    (net (code "258") (name "/RTM.P31_IO2_AB_B2_N") (class "Default")
      (node (ref "R358") (pin "1") (pinfunction "1_1") (pintype "passive"))
    )
    (net (code "259") (name "/RTM.P31_IO2_AB_B2_P") (class "Default")
      (node (ref "R362") (pin "1") (pinfunction "1_1") (pintype "passive"))
    )
    (net (code "260") (name "/RTM.P31_IO2_CD_B2_N") (class "Default")
      (node (ref "R374") (pin "1") (pinfunction "1_1") (pintype "passive"))
    )
    (net (code "261") (name "/RTM.P31_IO2_CD_B2_P") (class "Default")
      (node (ref "R378") (pin "1") (pinfunction "1_1") (pintype "passive"))
    )
    (net (code "262") (name "/RTM.P31_IO2_EF_B2_N") (class "Default")
      (node (ref "R442") (pin "1") (pinfunction "1_1") (pintype "passive"))
    )
    (net (code "263") (name "/RTM.P31_IO2_EF_B2_P") (class "Default")
      (node (ref "R450") (pin "1") (pinfunction "1_1") (pintype "passive"))
    )
    (net (code "264") (name "/RTM.P31_IO3_AB_B2_N") (class "Default")
      (node (ref "R534") (pin "1") (pinfunction "1_1") (pintype "passive"))
    )
    (net (code "265") (name "/RTM.P31_IO3_AB_B2_P") (class "Default")
      (node (ref "R538") (pin "1") (pinfunction "1_1") (pintype "passive"))
    )
    (net (code "266") (name "/RTM.P31_IO4_AB_B2_N") (class "Default")
      (node (ref "R526") (pin "1") (pinfunction "1_1") (pintype "passive"))
    )
    (net (code "267") (name "/RTM.P31_IO4_AB_B2_P") (class "Default")
      (node (ref "R530") (pin "1") (pinfunction "1_1") (pintype "passive"))
    )
    (net (code "268") (name "/RTM.P31_IO7_AB_B3_CC_N") (class "Default")
      (node (ref "R548") (pin "1") (pinfunction "1_1") (pintype "passive"))
    )
    (net (code "269") (name "/RTM.P31_IO7_AB_B3_CC_P") (class "Default")
      (node (ref "R549") (pin "1") (pinfunction "1_1") (pintype "passive"))
    )
    (net (code "270") (name "/RTM.P31_IO8_AB_B3_CC_N") (class "Default")
      (node (ref "R544") (pin "1") (pinfunction "1_1") (pintype "passive"))
    )
    (net (code "271") (name "/RTM.P31_IO8_AB_B3_CC_P") (class "Default")
      (node (ref "R546") (pin "1") (pinfunction "1_1") (pintype "passive"))
    )
    (net (code "272") (name "/VADJ2_PLL_DAC1_DIN") (class "Default")
      (node (ref "IC2") (pin "AF24") (pinfunction "IO_25_13_AF24") (pintype "bidirectional"))
    )
    (net (code "273") (name "/VADJ2_PLL_DAC1_SCLK") (class "Default")
      (node (ref "IC2") (pin "AJ24") (pinfunction "IO_0_12_AJ24") (pintype "bidirectional"))
    )
    (net (code "274") (name "/VADJ2_PLL_DAC2_DIN") (class "Default")
      (node (ref "IC2") (pin "AE32") (pinfunction "IO_L6P_T0_13_AE32") (pintype "bidirectional"))
    )
    (net (code "275") (name "/VADJ2_PLL_DAC2_SCLK") (class "Default")
      (node (ref "IC2") (pin "AL24") (pinfunction "IO_25_12_AL24") (pintype "bidirectional"))
    )
    (net (code "276") (name "/VADJ2_SI57X_OE") (class "Default")
      (node (ref "IC2") (pin "AD23") (pinfunction "IO_0_13_AD23") (pintype "bidirectional"))
    )
    (net (code "277") (name "/VADJ2_SI57X_PRI_SCL") (class "Default")
      (node (ref "IC2") (pin "V24") (pinfunction "IO_0_14_V24") (pintype "bidirectional"))
    )
    (net (code "278") (name "/VADJ2_SI57X_PRI_SDA") (class "Default")
      (node (ref "IC2") (pin "W24") (pinfunction "IO_25_14_W24") (pintype "bidirectional"))
    )
    (net (code "279") (name "/VADJ2_SI57X_PRI_TUNE{slash}SYNC") (class "Default")
      (node (ref "IC2") (pin "T24") (pinfunction "IO_0_15_T24") (pintype "bidirectional"))
    )
    (net (code "280") (name "/VADJ2_SI57X_SEC_TUNE{slash}SYNC") (class "Default")
      (node (ref "IC2") (pin "U24") (pinfunction "IO_25_15_U24") (pintype "bidirectional"))
    )
    (net (code "281") (name "/Vbias_bank14") (class "Default")
      (node (ref "C416") (pin "1") (pinfunction "1_1") (pintype "passive"))
      (node (ref "C459") (pin "1") (pinfunction "1_1") (pintype "passive"))
      (node (ref "C468") (pin "1") (pinfunction "1_1") (pintype "passive"))
      (node (ref "R123") (pin "2") (pinfunction "2_2") (pintype "passive"))
      (node (ref "R148") (pin "2") (pinfunction "2_2") (pintype "passive"))
      (node (ref "R149") (pin "2") (pinfunction "2_2") (pintype "passive"))
      (node (ref "R300") (pin "2") (pinfunction "2_2") (pintype "passive"))
      (node (ref "R306") (pin "2") (pinfunction "2_2") (pintype "passive"))
      (node (ref "R319") (pin "2") (pinfunction "2_2") (pintype "passive"))
    )
    (net (code "292") (name "GND") (class "Default")
      (node (ref "C124") (pin "2") (pinfunction "2_2") (pintype "passive"))
      (node (ref "C125") (pin "2") (pinfunction "2_2") (pintype "passive"))
      (node (ref "C129") (pin "2") (pinfunction "2_2") (pintype "passive"))
      (node (ref "C131") (pin "2") (pinfunction "2_2") (pintype "passive"))
      (node (ref "C132") (pin "2") (pinfunction "2_2") (pintype "passive"))
      (node (ref "C392") (pin "2") (pinfunction "2_2") (pintype "passive"))
      (node (ref "C416") (pin "2") (pinfunction "2_2") (pintype "passive"))
      (node (ref "C459") (pin "2") (pinfunction "2_2") (pintype "passive"))
      (node (ref "C468") (pin "2") (pinfunction "2_2") (pintype "passive"))
      (node (ref "R148") (pin "1") (pinfunction "1_1") (pintype "passive"))
      (node (ref "R180") (pin "2") (pinfunction "2_2") (pintype "passive"))
    )
    (net (code "293") (name "Net-(IC2C-IO_L12N_T1_MRCC_14)") (class "Default")
      (node (ref "IC2") (pin "Y31") (pinfunction "IO_L12N_T1_MRCC_14_Y31") (pintype "bidirectional"))
      (node (ref "R306") (pin "1") (pinfunction "1_1") (pintype "passive"))
      (node (ref "R318") (pin "2") (pinfunction "2_2") (pintype "passive"))
    )
    (net (code "294") (name "Net-(IC2C-IO_L12P_T1_MRCC_14)") (class "Default")
      (node (ref "IC2") (pin "Y30") (pinfunction "IO_L12P_T1_MRCC_14_Y30") (pintype "bidirectional"))
      (node (ref "R318") (pin "1") (pinfunction "1_1") (pintype "passive"))
      (node (ref "R319") (pin "1") (pinfunction "1_1") (pintype "passive"))
    )
    (net (code "295") (name "Net-(IC2C-IO_L13N_T2_MRCC_14)") (class "Default")
      (node (ref "IC2") (pin "AB30") (pinfunction "IO_L13N_T2_MRCC_14_AB30") (pintype "bidirectional"))
      (node (ref "R149") (pin "1") (pinfunction "1_1") (pintype "passive"))
      (node (ref "R150") (pin "2") (pinfunction "2_2") (pintype "passive"))
    )
    (net (code "296") (name "Net-(IC2C-IO_L13P_T2_MRCC_14)") (class "Default")
      (node (ref "IC2") (pin "AA30") (pinfunction "IO_L13P_T2_MRCC_14_AA30") (pintype "bidirectional"))
      (node (ref "R150") (pin "1") (pinfunction "1_1") (pintype "passive"))
      (node (ref "R300") (pin "1") (pinfunction "1_1") (pintype "passive"))
    )
    (net (code "297") (name "PVADJ2") (class "Default")
      (node (ref "R123") (pin "1") (pinfunction "1_1") (pintype "passive"))
      (node (ref "R270") (pin "1") (pinfunction "1_1") (pintype "passive"))
      (node (ref "R323") (pin "1") (pinfunction "1_1") (pintype "passive"))
    )
    (net (code "298") (name "unconnected-(IC2B-IO_L15N_T2_DQS_13-PadAE26)") (class "Default")
      (node (ref "IC2") (pin "AE26") (pinfunction "IO_L15N_T2_DQS_13_AE26") (pintype "bidirectional"))
    )
    (net (code "299") (name "unconnected-(IC2B-IO_L15P_T2_DQS_13-PadAD26)") (class "Default")
      (node (ref "IC2") (pin "AD26") (pinfunction "IO_L15P_T2_DQS_13_AD26") (pintype "bidirectional"))
    )
    (net (code "300") (name "unconnected-(IC2B-IO_L22N_T3_13-PadAD24)") (class "Default")
      (node (ref "IC2") (pin "AD24") (pinfunction "IO_L22N_T3_13_AD24") (pintype "bidirectional"))
    )
    (net (code "301") (name "unconnected-(IC2B-IO_L22P_T3_13-PadAC24)") (class "Default")
      (node (ref "IC2") (pin "AC24") (pinfunction "IO_L22P_T3_13_AC24") (pintype "bidirectional"))
    )
    (net (code "302") (name "unconnected-(IC2C-IO_L3N_T0_DQS_EMCCLK_14-PadY26)") (class "Default")
      (node (ref "IC2") (pin "Y26") (pinfunction "IO_L3N_T0_DQS_EMCCLK_14_Y26") (pintype "bidirectional"))
    )
    (net (code "303") (name "unconnected-(IC2C-IO_L19P_T3_A10_D26_14-PadAC28)") (class "Default")
      (node (ref "IC2") (pin "AC28") (pinfunction "IO_L19P_T3_A10_D26_14_AC28") (pintype "bidirectional"))
    )
    (net (code "304") (name "unconnected-(IC2D-IO_L6P_T0_15-PadR25)") (class "Default")
      (node (ref "IC2") (pin "R25") (pinfunction "IO_L6P_T0_15_R25") (pintype "bidirectional"))
    )
    (net (code "305") (name "unconnected-(IC2D-IO_L19P_T3_A22_15-PadT32)") (class "Default")
      (node (ref "IC2") (pin "T32") (pinfunction "IO_L19P_T3_A22_15_T32") (pintype "bidirectional"))
    )
  )
)
